# CARA_ctrl_v1_2.net
KiCad netlist of a schematic drawn in EAGLE
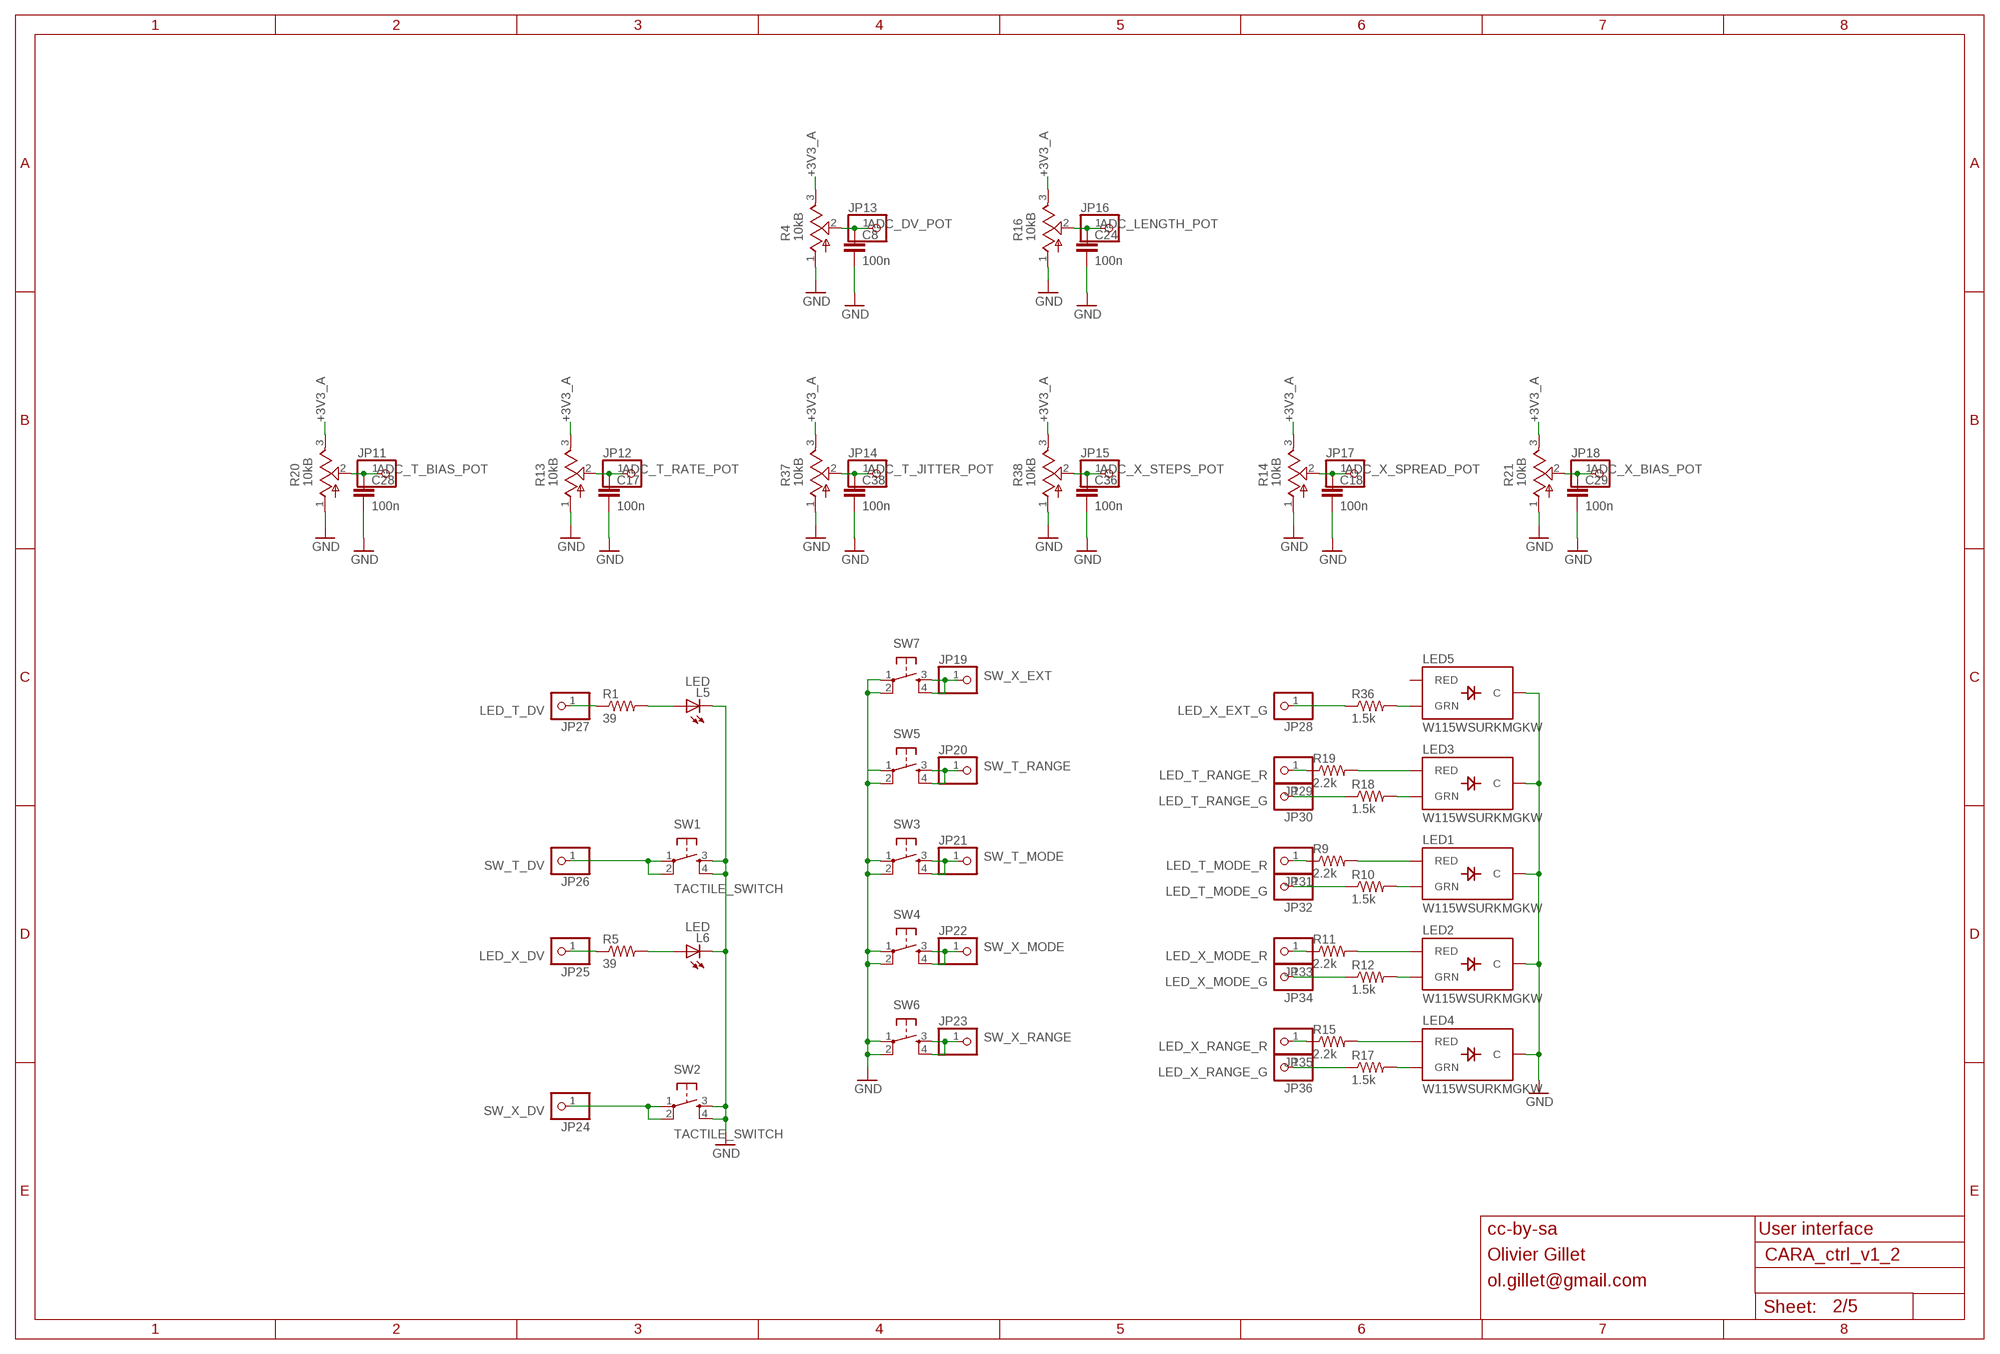
[diagram p0: schematic, sheet 2]
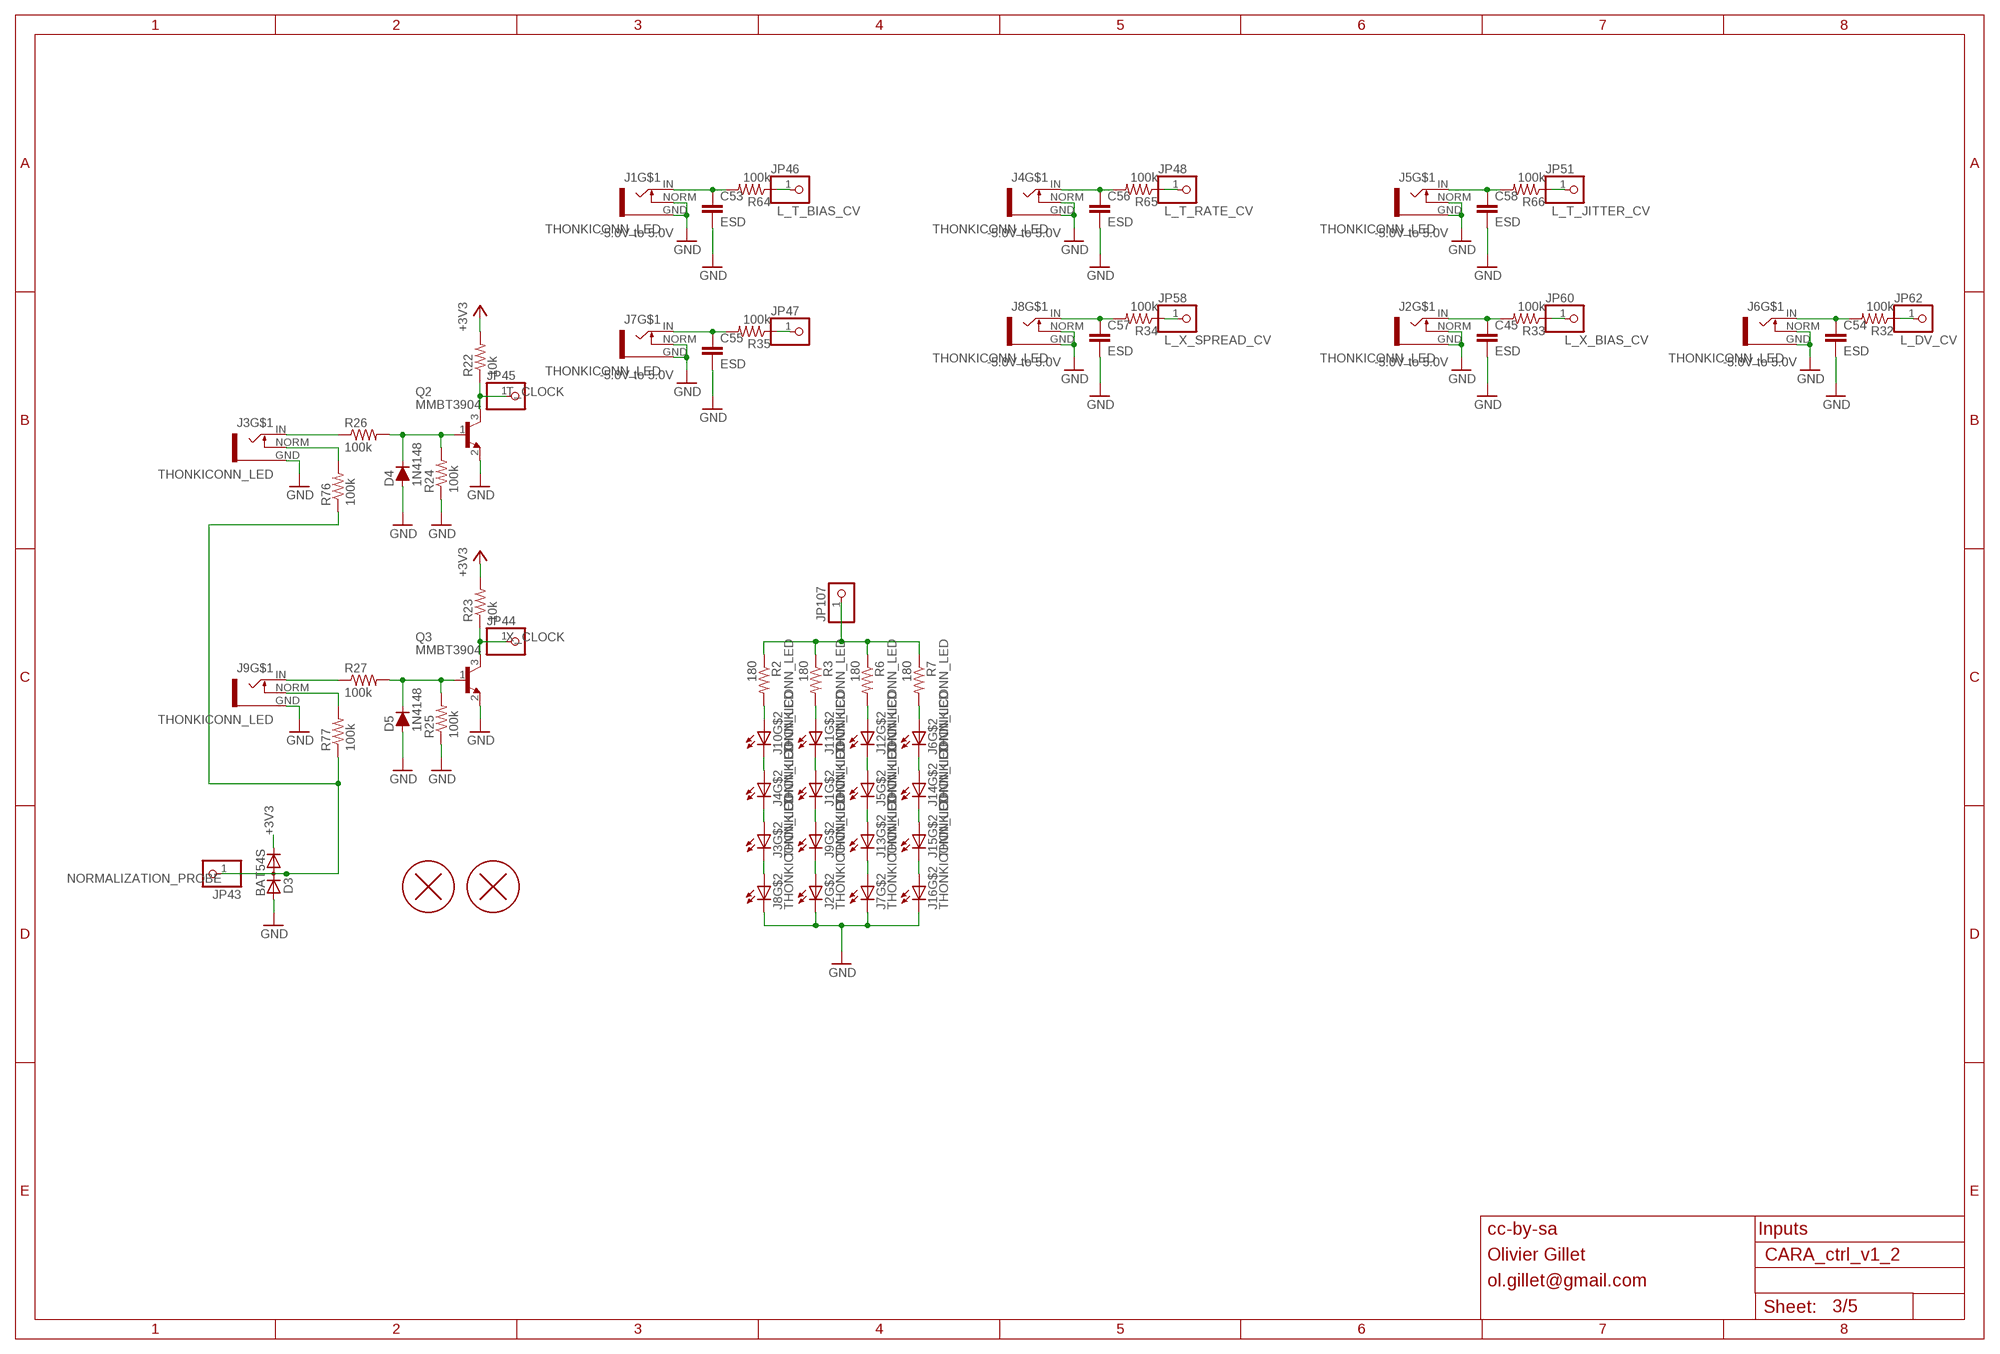
[diagram p1: schematic, sheet 3]
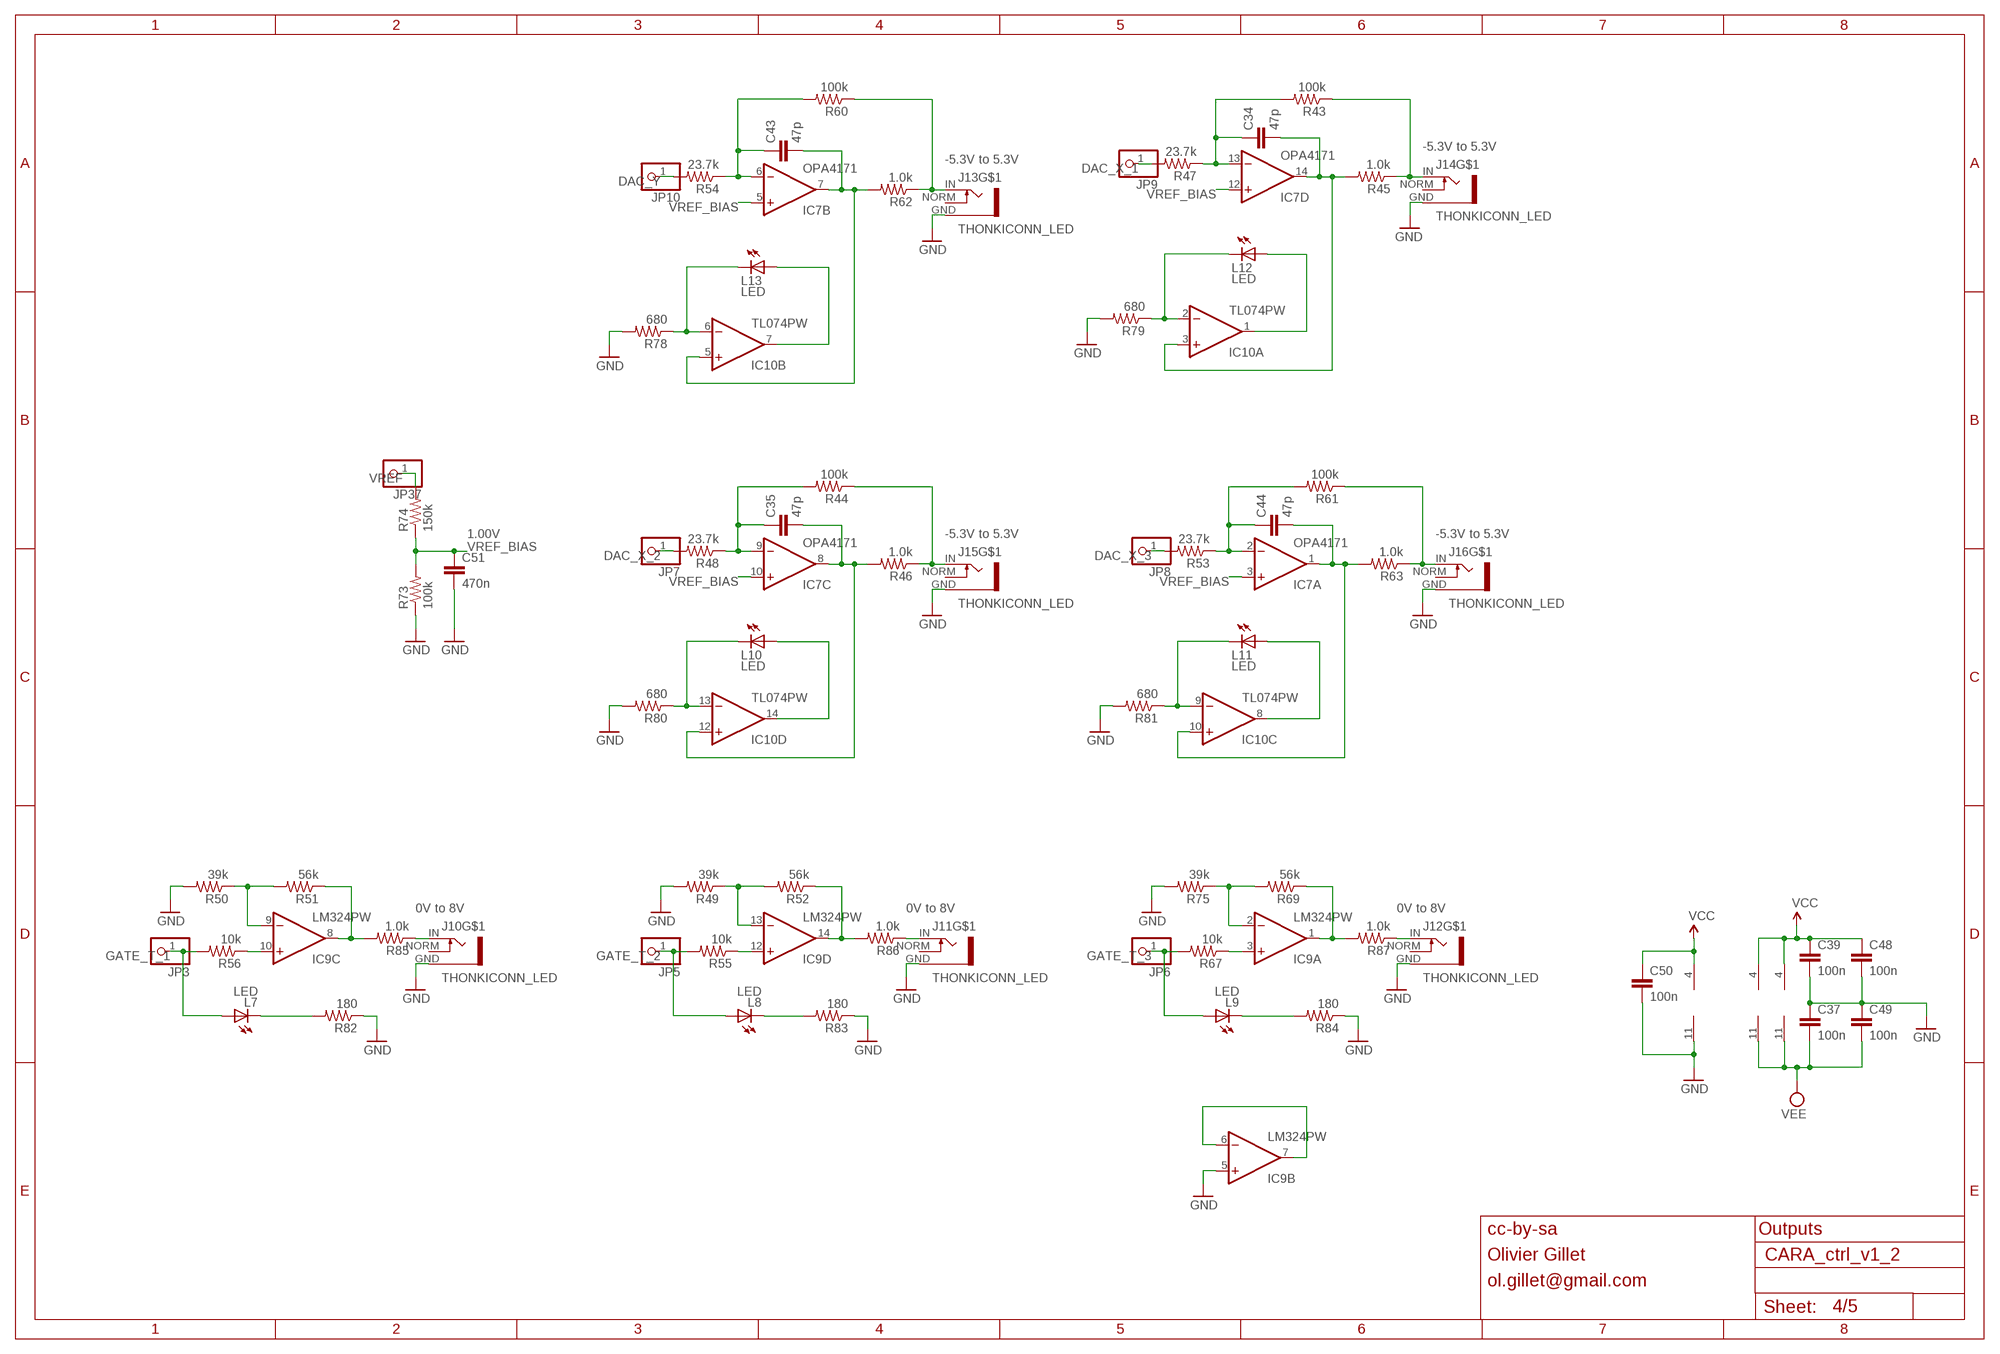
[diagram p2: schematic, sheet 4]
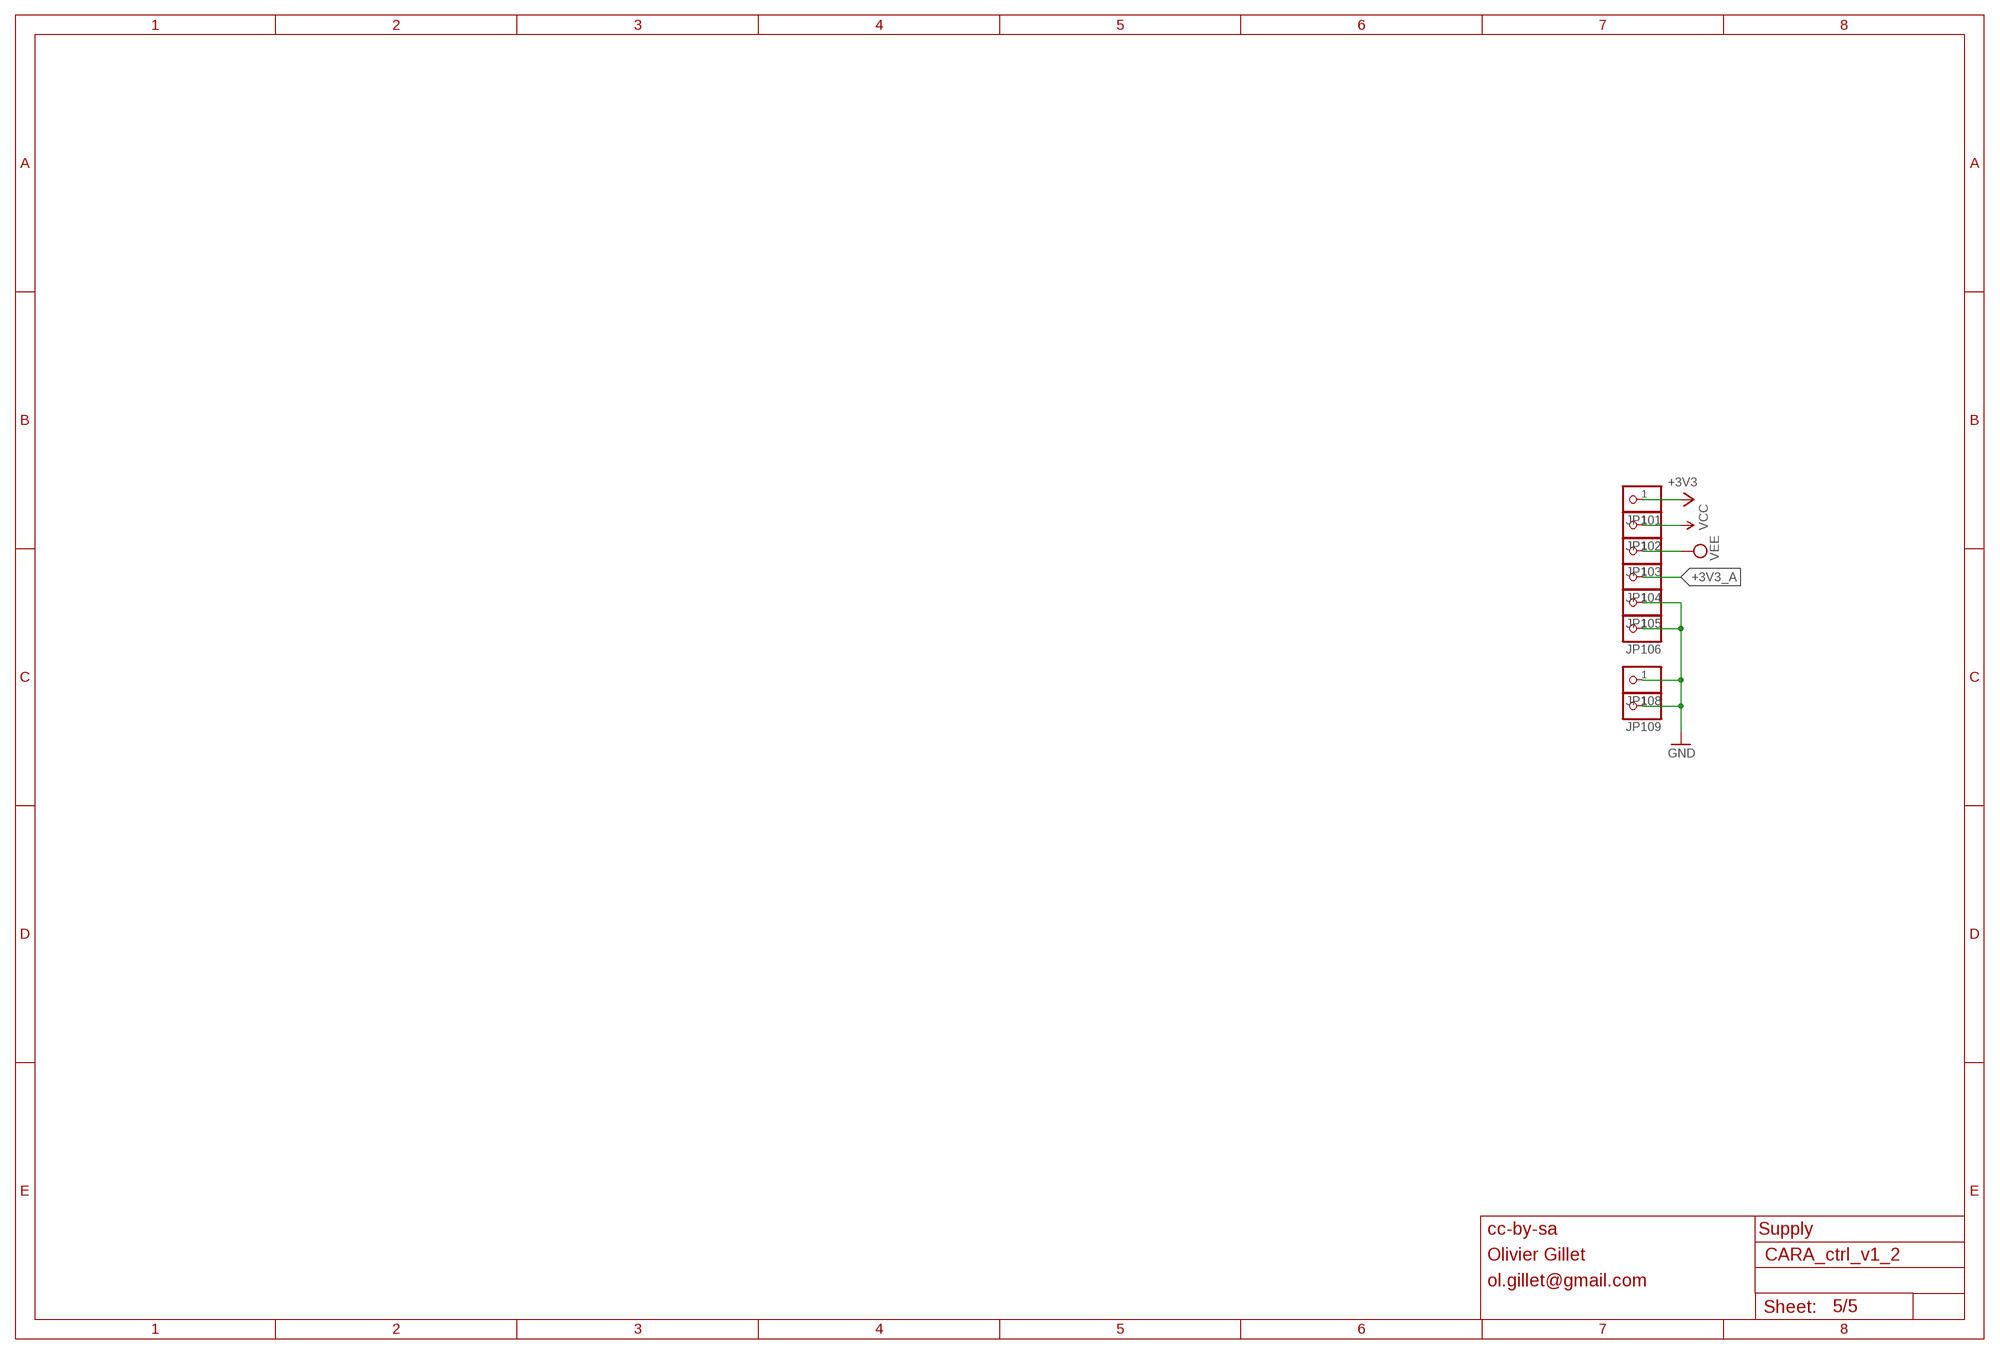
[diagram p3: schematic, sheet 5]

(export (version "E")
  (design (tool "Eeschema 10.0.6"))
  (components
    (comp (ref "C8")
      (value "100n")
      (footprint "eagle-import:RESISTOR_0603")
      (libsource (lib "eagle-import") (part "CAPACITOR"))
    )
    (comp (ref "C17")
      (value "100n")
      (footprint "eagle-import:RESISTOR_0603")
      (libsource (lib "eagle-import") (part "CAPACITOR"))
    )
    (comp (ref "C18")
      (value "100n")
      (footprint "eagle-import:RESISTOR_0603")
      (libsource (lib "eagle-import") (part "CAPACITOR"))
    )
    (comp (ref "C24")
      (value "100n")
      (footprint "eagle-import:RESISTOR_0603")
      (libsource (lib "eagle-import") (part "CAPACITOR"))
    )
    (comp (ref "C28")
      (value "100n")
      (footprint "eagle-import:RESISTOR_0603")
      (libsource (lib "eagle-import") (part "CAPACITOR"))
    )
    (comp (ref "C29")
      (value "100n")
      (footprint "eagle-import:RESISTOR_0603")
      (libsource (lib "eagle-import") (part "CAPACITOR"))
    )
    (comp (ref "C36")
      (value "100n")
      (footprint "eagle-import:RESISTOR_0603")
      (libsource (lib "eagle-import") (part "CAPACITOR"))
    )
    (comp (ref "C38")
      (value "100n")
      (footprint "eagle-import:RESISTOR_0603")
      (libsource (lib "eagle-import") (part "CAPACITOR"))
    )
    (comp (ref "JP11")
      (value "PINHD-1X1")
      (footprint "eagle-import:1X01")
      (libsource (lib "eagle-import") (part "PINHD-1X1"))
    )
    (comp (ref "JP12")
      (value "PINHD-1X1")
      (footprint "eagle-import:1X01")
      (libsource (lib "eagle-import") (part "PINHD-1X1"))
    )
    (comp (ref "JP13")
      (value "PINHD-1X1")
      (footprint "eagle-import:1X01")
      (libsource (lib "eagle-import") (part "PINHD-1X1"))
    )
    (comp (ref "JP14")
      (value "PINHD-1X1")
      (footprint "eagle-import:1X01")
      (libsource (lib "eagle-import") (part "PINHD-1X1"))
    )
    (comp (ref "JP15")
      (value "PINHD-1X1")
      (footprint "eagle-import:1X01")
      (libsource (lib "eagle-import") (part "PINHD-1X1"))
    )
    (comp (ref "JP16")
      (value "PINHD-1X1")
      (footprint "eagle-import:1X01")
      (libsource (lib "eagle-import") (part "PINHD-1X1"))
    )
    (comp (ref "JP17")
      (value "PINHD-1X1")
      (footprint "eagle-import:1X01")
      (libsource (lib "eagle-import") (part "PINHD-1X1"))
    )
    (comp (ref "JP18")
      (value "PINHD-1X1")
      (footprint "eagle-import:1X01")
      (libsource (lib "eagle-import") (part "PINHD-1X1"))
    )
    (comp (ref "JP19")
      (value "PINHD-1X1")
      (footprint "eagle-import:1X01")
      (libsource (lib "eagle-import") (part "PINHD-1X1"))
    )
    (comp (ref "JP20")
      (value "PINHD-1X1")
      (footprint "eagle-import:1X01")
      (libsource (lib "eagle-import") (part "PINHD-1X1"))
    )
    (comp (ref "JP21")
      (value "PINHD-1X1")
      (footprint "eagle-import:1X01")
      (libsource (lib "eagle-import") (part "PINHD-1X1"))
    )
    (comp (ref "JP22")
      (value "PINHD-1X1")
      (footprint "eagle-import:1X01")
      (libsource (lib "eagle-import") (part "PINHD-1X1"))
    )
    (comp (ref "JP23")
      (value "PINHD-1X1")
      (footprint "eagle-import:1X01")
      (libsource (lib "eagle-import") (part "PINHD-1X1"))
    )
    (comp (ref "JP24")
      (value "PINHD-1X1")
      (footprint "eagle-import:1X01")
      (libsource (lib "eagle-import") (part "PINHD-1X1"))
    )
    (comp (ref "JP25")
      (value "PINHD-1X1")
      (footprint "eagle-import:1X01")
      (libsource (lib "eagle-import") (part "PINHD-1X1"))
    )
    (comp (ref "JP26")
      (value "PINHD-1X1")
      (footprint "eagle-import:1X01")
      (libsource (lib "eagle-import") (part "PINHD-1X1"))
    )
    (comp (ref "JP27")
      (value "PINHD-1X1")
      (footprint "eagle-import:1X01")
      (libsource (lib "eagle-import") (part "PINHD-1X1"))
    )
    (comp (ref "JP28")
      (value "PINHD-1X1")
      (footprint "eagle-import:1X01")
      (libsource (lib "eagle-import") (part "PINHD-1X1"))
    )
    (comp (ref "JP29")
      (value "PINHD-1X1")
      (footprint "eagle-import:1X01")
      (libsource (lib "eagle-import") (part "PINHD-1X1"))
    )
    (comp (ref "JP30")
      (value "PINHD-1X1")
      (footprint "eagle-import:1X01")
      (libsource (lib "eagle-import") (part "PINHD-1X1"))
    )
    (comp (ref "JP31")
      (value "PINHD-1X1")
      (footprint "eagle-import:1X01")
      (libsource (lib "eagle-import") (part "PINHD-1X1"))
    )
    (comp (ref "JP32")
      (value "PINHD-1X1")
      (footprint "eagle-import:1X01")
      (libsource (lib "eagle-import") (part "PINHD-1X1"))
    )
    (comp (ref "JP33")
      (value "PINHD-1X1")
      (footprint "eagle-import:1X01")
      (libsource (lib "eagle-import") (part "PINHD-1X1"))
    )
    (comp (ref "JP34")
      (value "PINHD-1X1")
      (footprint "eagle-import:1X01")
      (libsource (lib "eagle-import") (part "PINHD-1X1"))
    )
    (comp (ref "JP35")
      (value "PINHD-1X1")
      (footprint "eagle-import:1X01")
      (libsource (lib "eagle-import") (part "PINHD-1X1"))
    )
    (comp (ref "JP36")
      (value "PINHD-1X1")
      (footprint "eagle-import:1X01")
      (libsource (lib "eagle-import") (part "PINHD-1X1"))
    )
    (comp (ref "L5")
      (value "LED")
      (footprint "eagle-import:LED_3MM")
      (libsource (lib "eagle-import") (part "LED"))
    )
    (comp (ref "L6")
      (value "LED")
      (footprint "eagle-import:LED_3MM")
      (libsource (lib "eagle-import") (part "LED"))
    )
    (comp (ref "LED1")
      (value "W115WSURKMGKW")
      (footprint "eagle-import:LED_BICOLOR")
      (libsource (lib "eagle-import") (part "LED_BICOLOR_THROUGHHOLE"))
    )
    (comp (ref "LED2")
      (value "W115WSURKMGKW")
      (footprint "eagle-import:LED_BICOLOR")
      (libsource (lib "eagle-import") (part "LED_BICOLOR_THROUGHHOLE"))
    )
    (comp (ref "LED3")
      (value "W115WSURKMGKW")
      (footprint "eagle-import:LED_BICOLOR")
      (libsource (lib "eagle-import") (part "LED_BICOLOR_THROUGHHOLE"))
    )
    (comp (ref "LED4")
      (value "W115WSURKMGKW")
      (footprint "eagle-import:LED_BICOLOR")
      (libsource (lib "eagle-import") (part "LED_BICOLOR_THROUGHHOLE"))
    )
    (comp (ref "LED5")
      (value "W115WSURKMGKW")
      (footprint "eagle-import:LED_BICOLOR")
      (libsource (lib "eagle-import") (part "LED_BICOLOR_THROUGHHOLE"))
    )
    (comp (ref "R1")
      (value "39")
      (footprint "eagle-import:RESISTOR_0603")
      (libsource (lib "eagle-import") (part "RESISTOR"))
    )
    (comp (ref "R4")
      (value "10kB")
      (footprint "eagle-import:ALPS_POT_VERTICAL")
      (libsource (lib "eagle-import") (part "POT_VERTICAL"))
    )
    (comp (ref "R5")
      (value "39")
      (footprint "eagle-import:RESISTOR_0603")
      (libsource (lib "eagle-import") (part "RESISTOR"))
    )
    (comp (ref "R9")
      (value "2.2k")
      (footprint "eagle-import:RESISTOR_0603")
      (libsource (lib "eagle-import") (part "RESISTOR"))
    )
    (comp (ref "R10")
      (value "1.5k")
      (footprint "eagle-import:RESISTOR_0603")
      (libsource (lib "eagle-import") (part "RESISTOR"))
    )
    (comp (ref "R11")
      (value "2.2k")
      (footprint "eagle-import:RESISTOR_0603")
      (libsource (lib "eagle-import") (part "RESISTOR"))
    )
    (comp (ref "R12")
      (value "1.5k")
      (footprint "eagle-import:RESISTOR_0603")
      (libsource (lib "eagle-import") (part "RESISTOR"))
    )
    (comp (ref "R13")
      (value "10kB")
      (footprint "eagle-import:ALPS_POT_VERTICAL")
      (libsource (lib "eagle-import") (part "POT_VERTICAL"))
    )
    (comp (ref "R14")
      (value "10kB")
      (footprint "eagle-import:ALPS_POT_VERTICAL")
      (libsource (lib "eagle-import") (part "POT_VERTICAL"))
    )
    (comp (ref "R15")
      (value "2.2k")
      (footprint "eagle-import:RESISTOR_0603")
      (libsource (lib "eagle-import") (part "RESISTOR"))
    )
    (comp (ref "R16")
      (value "10kB")
      (footprint "eagle-import:ALPS_POT_VERTICAL")
      (libsource (lib "eagle-import") (part "POT_VERTICAL"))
    )
    (comp (ref "R17")
      (value "1.5k")
      (footprint "eagle-import:RESISTOR_0603")
      (libsource (lib "eagle-import") (part "RESISTOR"))
    )
    (comp (ref "R18")
      (value "1.5k")
      (footprint "eagle-import:RESISTOR_0603")
      (libsource (lib "eagle-import") (part "RESISTOR"))
    )
    (comp (ref "R19")
      (value "2.2k")
      (footprint "eagle-import:RESISTOR_0603")
      (libsource (lib "eagle-import") (part "RESISTOR"))
    )
    (comp (ref "R20")
      (value "10kB")
      (footprint "eagle-import:ALPS_POT_VERTICAL")
      (libsource (lib "eagle-import") (part "POT_VERTICAL"))
    )
    (comp (ref "R21")
      (value "10kB")
      (footprint "eagle-import:ALPS_POT_VERTICAL")
      (libsource (lib "eagle-import") (part "POT_VERTICAL"))
    )
    (comp (ref "R36")
      (value "1.5k")
      (footprint "eagle-import:RESISTOR_0603")
      (libsource (lib "eagle-import") (part "RESISTOR"))
    )
    (comp (ref "R37")
      (value "10kB")
      (footprint "eagle-import:ALPS_POT_VERTICAL")
      (libsource (lib "eagle-import") (part "POT_VERTICAL"))
    )
    (comp (ref "R38")
      (value "10kB")
      (footprint "eagle-import:ALPS_POT_VERTICAL")
      (libsource (lib "eagle-import") (part "POT_VERTICAL"))
    )
    (comp (ref "SW1")
      (value "TACTILE_SWITCH")
      (footprint "eagle-import:TACTILE-PTH")
      (libsource (lib "eagle-import") (part "TACTILE_SWITCH"))
    )
    (comp (ref "SW2")
      (value "TACTILE_SWITCH")
      (footprint "eagle-import:TACTILE-PTH")
      (libsource (lib "eagle-import") (part "TACTILE_SWITCH"))
    )
    (comp (ref "SW3")
      (value "TACTILE_SWITCH")
      (footprint "eagle-import:TACTILE-PTH")
      (libsource (lib "eagle-import") (part "TACTILE_SWITCH"))
    )
    (comp (ref "SW4")
      (value "TACTILE_SWITCH")
      (footprint "eagle-import:TACTILE-PTH")
      (libsource (lib "eagle-import") (part "TACTILE_SWITCH"))
    )
    (comp (ref "SW5")
      (value "TACTILE_SWITCH")
      (footprint "eagle-import:TACTILE-PTH")
      (libsource (lib "eagle-import") (part "TACTILE_SWITCH"))
    )
    (comp (ref "SW6")
      (value "TACTILE_SWITCH")
      (footprint "eagle-import:TACTILE-PTH")
      (libsource (lib "eagle-import") (part "TACTILE_SWITCH"))
    )
    (comp (ref "SW7")
      (value "TACTILE_SWITCH")
      (footprint "eagle-import:TACTILE-PTH")
      (libsource (lib "eagle-import") (part "TACTILE_SWITCH"))
    )
    (comp (ref "JP101")
      (value "PINHD-1X1")
      (footprint "eagle-import:1X01")
      (libsource (lib "eagle-import") (part "PINHD-1X1"))
    )
    (comp (ref "JP102")
      (value "PINHD-1X1")
      (footprint "eagle-import:1X01")
      (libsource (lib "eagle-import") (part "PINHD-1X1"))
    )
    (comp (ref "JP103")
      (value "PINHD-1X1")
      (footprint "eagle-import:1X01")
      (libsource (lib "eagle-import") (part "PINHD-1X1"))
    )
    (comp (ref "JP104")
      (value "PINHD-1X1")
      (footprint "eagle-import:1X01")
      (libsource (lib "eagle-import") (part "PINHD-1X1"))
    )
    (comp (ref "JP105")
      (value "PINHD-1X1")
      (footprint "eagle-import:1X01")
      (libsource (lib "eagle-import") (part "PINHD-1X1"))
    )
    (comp (ref "JP106")
      (value "PINHD-1X1")
      (footprint "eagle-import:1X01")
      (libsource (lib "eagle-import") (part "PINHD-1X1"))
    )
    (comp (ref "JP108")
      (value "PINHD-1X1")
      (footprint "eagle-import:1X01")
      (libsource (lib "eagle-import") (part "PINHD-1X1"))
    )
    (comp (ref "JP109")
      (value "PINHD-1X1")
      (footprint "eagle-import:1X01")
      (libsource (lib "eagle-import") (part "PINHD-1X1"))
    )
    (comp (ref "C45")
      (value "ESD")
      (footprint "eagle-import:RESISTOR_0603")
      (libsource (lib "eagle-import") (part "CAPACITOR"))
    )
    (comp (ref "C53")
      (value "ESD")
      (footprint "eagle-import:RESISTOR_0603")
      (libsource (lib "eagle-import") (part "CAPACITOR"))
    )
    (comp (ref "C54")
      (value "ESD")
      (footprint "eagle-import:RESISTOR_0603")
      (libsource (lib "eagle-import") (part "CAPACITOR"))
    )
    (comp (ref "C55")
      (value "ESD")
      (footprint "eagle-import:RESISTOR_0603")
      (libsource (lib "eagle-import") (part "CAPACITOR"))
    )
    (comp (ref "C56")
      (value "ESD")
      (footprint "eagle-import:RESISTOR_0603")
      (libsource (lib "eagle-import") (part "CAPACITOR"))
    )
    (comp (ref "C57")
      (value "ESD")
      (footprint "eagle-import:RESISTOR_0603")
      (libsource (lib "eagle-import") (part "CAPACITOR"))
    )
    (comp (ref "C58")
      (value "ESD")
      (footprint "eagle-import:RESISTOR_0603")
      (libsource (lib "eagle-import") (part "CAPACITOR"))
    )
    (comp (ref "D3")
      (value "BAT54S")
      (footprint "eagle-import:SOT23")
      (libsource (lib "eagle-import") (part "DIODE_2CACA-SOT23"))
    )
    (comp (ref "D4")
      (value "1N4148")
      (footprint "eagle-import:SOD123")
      (libsource (lib "eagle-import") (part "DIODE"))
    )
    (comp (ref "D5")
      (value "1N4148")
      (footprint "eagle-import:SOD123")
      (libsource (lib "eagle-import") (part "DIODE"))
    )
    (comp (ref "H1")
      (value "PCB_SCREW")
      (footprint "eagle-import:PCB_SCREW")
      (libsource (lib "eagle-import") (part "PCB_SCREW"))
    )
    (comp (ref "H2")
      (value "PCB_SCREW")
      (footprint "eagle-import:PCB_SCREW")
      (libsource (lib "eagle-import") (part "PCB_SCREW"))
    )
    (comp (ref "J1")
      (value "THONKICONN_LED")
      (footprint "eagle-import:LED_JACK")
      (libsource (lib "eagle-import") (part "THONKICONN_LED"))
    )
    (comp (ref "J2")
      (value "THONKICONN_LED")
      (footprint "eagle-import:LED_JACK")
      (libsource (lib "eagle-import") (part "THONKICONN_LED"))
    )
    (comp (ref "J3")
      (value "THONKICONN_LED")
      (footprint "eagle-import:LED_JACK")
      (libsource (lib "eagle-import") (part "THONKICONN_LED"))
    )
    (comp (ref "J4")
      (value "THONKICONN_LED")
      (footprint "eagle-import:LED_JACK")
      (libsource (lib "eagle-import") (part "THONKICONN_LED"))
    )
    (comp (ref "J5")
      (value "THONKICONN_LED")
      (footprint "eagle-import:LED_JACK")
      (libsource (lib "eagle-import") (part "THONKICONN_LED"))
    )
    (comp (ref "J6")
      (value "THONKICONN_LED")
      (footprint "eagle-import:LED_JACK")
      (libsource (lib "eagle-import") (part "THONKICONN_LED"))
    )
    (comp (ref "J7")
      (value "THONKICONN_LED")
      (footprint "eagle-import:LED_JACK")
      (libsource (lib "eagle-import") (part "THONKICONN_LED"))
    )
    (comp (ref "J8")
      (value "THONKICONN_LED")
      (footprint "eagle-import:LED_JACK")
      (libsource (lib "eagle-import") (part "THONKICONN_LED"))
    )
    (comp (ref "J9")
      (value "THONKICONN_LED")
      (footprint "eagle-import:LED_JACK")
      (libsource (lib "eagle-import") (part "THONKICONN_LED"))
    )
    (comp (ref "J10")
      (value "THONKICONN_LED")
      (footprint "eagle-import:LED_JACK")
      (libsource (lib "eagle-import") (part "THONKICONN_LED"))
    )
    (comp (ref "J11")
      (value "THONKICONN_LED")
      (footprint "eagle-import:LED_JACK")
      (libsource (lib "eagle-import") (part "THONKICONN_LED"))
    )
    (comp (ref "J12")
      (value "THONKICONN_LED")
      (footprint "eagle-import:LED_JACK")
      (libsource (lib "eagle-import") (part "THONKICONN_LED"))
    )
    (comp (ref "J13")
      (value "THONKICONN_LED")
      (footprint "eagle-import:LED_JACK")
      (libsource (lib "eagle-import") (part "THONKICONN_LED"))
    )
    (comp (ref "J14")
      (value "THONKICONN_LED")
      (footprint "eagle-import:LED_JACK")
      (libsource (lib "eagle-import") (part "THONKICONN_LED"))
    )
    (comp (ref "J15")
      (value "THONKICONN_LED")
      (footprint "eagle-import:LED_JACK")
      (libsource (lib "eagle-import") (part "THONKICONN_LED"))
    )
    (comp (ref "J16")
      (value "THONKICONN_LED")
      (footprint "eagle-import:LED_JACK")
      (libsource (lib "eagle-import") (part "THONKICONN_LED"))
    )
    (comp (ref "JP43")
      (value "PINHD-1X1")
      (footprint "eagle-import:1X01")
      (libsource (lib "eagle-import") (part "PINHD-1X1"))
    )
    (comp (ref "JP44")
      (value "PINHD-1X1")
      (footprint "eagle-import:1X01")
      (libsource (lib "eagle-import") (part "PINHD-1X1"))
    )
    (comp (ref "JP45")
      (value "PINHD-1X1")
      (footprint "eagle-import:1X01")
      (libsource (lib "eagle-import") (part "PINHD-1X1"))
    )
    (comp (ref "JP46")
      (value "PINHD-1X1")
      (footprint "eagle-import:1X01")
      (libsource (lib "eagle-import") (part "PINHD-1X1"))
    )
    (comp (ref "JP47")
      (value "PINHD-1X1")
      (footprint "eagle-import:1X01")
      (libsource (lib "eagle-import") (part "PINHD-1X1"))
    )
    (comp (ref "JP48")
      (value "PINHD-1X1")
      (footprint "eagle-import:1X01")
      (libsource (lib "eagle-import") (part "PINHD-1X1"))
    )
    (comp (ref "JP51")
      (value "PINHD-1X1")
      (footprint "eagle-import:1X01")
      (libsource (lib "eagle-import") (part "PINHD-1X1"))
    )
    (comp (ref "JP58")
      (value "PINHD-1X1")
      (footprint "eagle-import:1X01")
      (libsource (lib "eagle-import") (part "PINHD-1X1"))
    )
    (comp (ref "JP60")
      (value "PINHD-1X1")
      (footprint "eagle-import:1X01")
      (libsource (lib "eagle-import") (part "PINHD-1X1"))
    )
    (comp (ref "JP62")
      (value "PINHD-1X1")
      (footprint "eagle-import:1X01")
      (libsource (lib "eagle-import") (part "PINHD-1X1"))
    )
    (comp (ref "JP107")
      (value "PINHD-1X1")
      (footprint "eagle-import:1X01")
      (libsource (lib "eagle-import") (part "PINHD-1X1"))
    )
    (comp (ref "Q2")
      (value "MMBT3904")
      (footprint "eagle-import:SOT23")
      (libsource (lib "eagle-import") (part "MMBT3904SOT23"))
    )
    (comp (ref "Q3")
      (value "MMBT3904")
      (footprint "eagle-import:SOT23")
      (libsource (lib "eagle-import") (part "MMBT3904SOT23"))
    )
    (comp (ref "R2")
      (value "180")
      (footprint "eagle-import:RESISTOR_0603")
      (libsource (lib "eagle-import") (part "RESISTOR"))
    )
    (comp (ref "R3")
      (value "180")
      (footprint "eagle-import:RESISTOR_0603")
      (libsource (lib "eagle-import") (part "RESISTOR"))
    )
    (comp (ref "R6")
      (value "180")
      (footprint "eagle-import:RESISTOR_0603")
      (libsource (lib "eagle-import") (part "RESISTOR"))
    )
    (comp (ref "R7")
      (value "180")
      (footprint "eagle-import:RESISTOR_0603")
      (libsource (lib "eagle-import") (part "RESISTOR"))
    )
    (comp (ref "R22")
      (value "10k")
      (footprint "eagle-import:RESISTOR_0603")
      (libsource (lib "eagle-import") (part "RESISTOR"))
    )
    (comp (ref "R23")
      (value "10k")
      (footprint "eagle-import:RESISTOR_0603")
      (libsource (lib "eagle-import") (part "RESISTOR"))
    )
    (comp (ref "R24")
      (value "100k")
      (footprint "eagle-import:RESISTOR_0603")
      (libsource (lib "eagle-import") (part "RESISTOR"))
    )
    (comp (ref "R25")
      (value "100k")
      (footprint "eagle-import:RESISTOR_0603")
      (libsource (lib "eagle-import") (part "RESISTOR"))
    )
    (comp (ref "R26")
      (value "100k")
      (footprint "eagle-import:RESISTOR_0603")
      (libsource (lib "eagle-import") (part "RESISTOR"))
    )
    (comp (ref "R27")
      (value "100k")
      (footprint "eagle-import:RESISTOR_0603")
      (libsource (lib "eagle-import") (part "RESISTOR"))
    )
    (comp (ref "R32")
      (value "100k")
      (footprint "eagle-import:RESISTOR_0603")
      (libsource (lib "eagle-import") (part "RESISTOR"))
    )
    (comp (ref "R33")
      (value "100k")
      (footprint "eagle-import:RESISTOR_0603")
      (libsource (lib "eagle-import") (part "RESISTOR"))
    )
    (comp (ref "R34")
      (value "100k")
      (footprint "eagle-import:RESISTOR_0603")
      (libsource (lib "eagle-import") (part "RESISTOR"))
    )
    (comp (ref "R35")
      (value "100k")
      (footprint "eagle-import:RESISTOR_0603")
      (libsource (lib "eagle-import") (part "RESISTOR"))
    )
    (comp (ref "R64")
      (value "100k")
      (footprint "eagle-import:RESISTOR_0603")
      (libsource (lib "eagle-import") (part "RESISTOR"))
    )
    (comp (ref "R65")
      (value "100k")
      (footprint "eagle-import:RESISTOR_0603")
      (libsource (lib "eagle-import") (part "RESISTOR"))
    )
    (comp (ref "R66")
      (value "100k")
      (footprint "eagle-import:RESISTOR_0603")
      (libsource (lib "eagle-import") (part "RESISTOR"))
    )
    (comp (ref "R76")
      (value "100k")
      (footprint "eagle-import:RESISTOR_0603")
      (libsource (lib "eagle-import") (part "RESISTOR"))
    )
    (comp (ref "R77")
      (value "100k")
      (footprint "eagle-import:RESISTOR_0603")
      (libsource (lib "eagle-import") (part "RESISTOR"))
    )
    (comp (ref "C34")
      (value "47p")
      (footprint "eagle-import:RESISTOR_0603")
      (libsource (lib "eagle-import") (part "CAPACITOR"))
    )
    (comp (ref "C35")
      (value "47p")
      (footprint "eagle-import:RESISTOR_0603")
      (libsource (lib "eagle-import") (part "CAPACITOR"))
    )
    (comp (ref "C37")
      (value "100n")
      (footprint "eagle-import:RESISTOR_0603")
      (libsource (lib "eagle-import") (part "CAPACITOR"))
    )
    (comp (ref "C39")
      (value "100n")
      (footprint "eagle-import:RESISTOR_0603")
      (libsource (lib "eagle-import") (part "CAPACITOR"))
    )
    (comp (ref "C43")
      (value "47p")
      (footprint "eagle-import:RESISTOR_0603")
      (libsource (lib "eagle-import") (part "CAPACITOR"))
    )
    (comp (ref "C44")
      (value "47p")
      (footprint "eagle-import:RESISTOR_0603")
      (libsource (lib "eagle-import") (part "CAPACITOR"))
    )
    (comp (ref "C48")
      (value "100n")
      (footprint "eagle-import:RESISTOR_0603")
      (libsource (lib "eagle-import") (part "CAPACITOR"))
    )
    (comp (ref "C49")
      (value "100n")
      (footprint "eagle-import:RESISTOR_0603")
      (libsource (lib "eagle-import") (part "CAPACITOR"))
    )
    (comp (ref "C50")
      (value "100n")
      (footprint "eagle-import:RESISTOR_0603")
      (libsource (lib "eagle-import") (part "CAPACITOR"))
    )
    (comp (ref "C51")
      (value "470n")
      (footprint "eagle-import:RESISTOR_0603")
      (libsource (lib "eagle-import") (part "CAPACITOR"))
    )
    (comp (ref "IC7")
      (value "OPA4171")
      (footprint "eagle-import:TSSOP14_065")
      (libsource (lib "eagle-import") (part "TL074PW"))
    )
    (comp (ref "IC9")
      (value "LM324PW")
      (footprint "eagle-import:TSSOP14_065")
      (libsource (lib "eagle-import") (part "TL074PW"))
    )
    (comp (ref "IC10")
      (value "TL074PW")
      (footprint "eagle-import:TSSOP14_065")
      (libsource (lib "eagle-import") (part "TL074PW"))
    )
    (comp (ref "JP3")
      (value "PINHD-1X1")
      (footprint "eagle-import:1X01")
      (libsource (lib "eagle-import") (part "PINHD-1X1"))
    )
    (comp (ref "JP5")
      (value "PINHD-1X1")
      (footprint "eagle-import:1X01")
      (libsource (lib "eagle-import") (part "PINHD-1X1"))
    )
    (comp (ref "JP6")
      (value "PINHD-1X1")
      (footprint "eagle-import:1X01")
      (libsource (lib "eagle-import") (part "PINHD-1X1"))
    )
    (comp (ref "JP7")
      (value "PINHD-1X1")
      (footprint "eagle-import:1X01")
      (libsource (lib "eagle-import") (part "PINHD-1X1"))
    )
    (comp (ref "JP8")
      (value "PINHD-1X1")
      (footprint "eagle-import:1X01")
      (libsource (lib "eagle-import") (part "PINHD-1X1"))
    )
    (comp (ref "JP9")
      (value "PINHD-1X1")
      (footprint "eagle-import:1X01")
      (libsource (lib "eagle-import") (part "PINHD-1X1"))
    )
    (comp (ref "JP10")
      (value "PINHD-1X1")
      (footprint "eagle-import:1X01")
      (libsource (lib "eagle-import") (part "PINHD-1X1"))
    )
    (comp (ref "JP37")
      (value "PINHD-1X1")
      (footprint "eagle-import:1X01")
      (libsource (lib "eagle-import") (part "PINHD-1X1"))
    )
    (comp (ref "L7")
      (value "LED")
      (footprint "eagle-import:LED_3MM")
      (libsource (lib "eagle-import") (part "LED"))
    )
    (comp (ref "L8")
      (value "LED")
      (footprint "eagle-import:LED_3MM")
      (libsource (lib "eagle-import") (part "LED"))
    )
    (comp (ref "L9")
      (value "LED")
      (footprint "eagle-import:LED_3MM")
      (libsource (lib "eagle-import") (part "LED"))
    )
    (comp (ref "L10")
      (value "LED")
      (footprint "eagle-import:LED_3MM")
      (libsource (lib "eagle-import") (part "LED"))
    )
    (comp (ref "L11")
      (value "LED")
      (footprint "eagle-import:LED_3MM")
      (libsource (lib "eagle-import") (part "LED"))
    )
    (comp (ref "L12")
      (value "LED")
      (footprint "eagle-import:LED_3MM")
      (libsource (lib "eagle-import") (part "LED"))
    )
    (comp (ref "L13")
      (value "LED")
      (footprint "eagle-import:LED_3MM")
      (libsource (lib "eagle-import") (part "LED"))
    )
    (comp (ref "R43")
      (value "100k")
      (footprint "eagle-import:RESISTOR_0603")
      (libsource (lib "eagle-import") (part "RESISTOR"))
    )
    (comp (ref "R44")
      (value "100k")
      (footprint "eagle-import:RESISTOR_0603")
      (libsource (lib "eagle-import") (part "RESISTOR"))
    )
    (comp (ref "R45")
      (value "1.0k")
      (footprint "eagle-import:RESISTOR_0603")
      (libsource (lib "eagle-import") (part "RESISTOR"))
    )
    (comp (ref "R46")
      (value "1.0k")
      (footprint "eagle-import:RESISTOR_0603")
      (libsource (lib "eagle-import") (part "RESISTOR"))
    )
    (comp (ref "R47")
      (value "23.7k")
      (footprint "eagle-import:RESISTOR_0603")
      (libsource (lib "eagle-import") (part "RESISTOR"))
    )
    (comp (ref "R48")
      (value "23.7k")
      (footprint "eagle-import:RESISTOR_0603")
      (libsource (lib "eagle-import") (part "RESISTOR"))
    )
    (comp (ref "R49")
      (value "39k")
      (footprint "eagle-import:RESISTOR_0603")
      (libsource (lib "eagle-import") (part "RESISTOR"))
    )
    (comp (ref "R50")
      (value "39k")
      (footprint "eagle-import:RESISTOR_0603")
      (libsource (lib "eagle-import") (part "RESISTOR"))
    )
    (comp (ref "R51")
      (value "56k")
      (footprint "eagle-import:RESISTOR_0603")
      (libsource (lib "eagle-import") (part "RESISTOR"))
    )
    (comp (ref "R52")
      (value "56k")
      (footprint "eagle-import:RESISTOR_0603")
      (libsource (lib "eagle-import") (part "RESISTOR"))
    )
    (comp (ref "R53")
      (value "23.7k")
      (footprint "eagle-import:RESISTOR_0603")
      (libsource (lib "eagle-import") (part "RESISTOR"))
    )
    (comp (ref "R54")
      (value "23.7k")
      (footprint "eagle-import:RESISTOR_0603")
      (libsource (lib "eagle-import") (part "RESISTOR"))
    )
    (comp (ref "R55")
      (value "10k")
      (footprint "eagle-import:RESISTOR_0603")
      (libsource (lib "eagle-import") (part "RESISTOR"))
    )
    (comp (ref "R56")
      (value "10k")
      (footprint "eagle-import:RESISTOR_0603")
      (libsource (lib "eagle-import") (part "RESISTOR"))
    )
    (comp (ref "R60")
      (value "100k")
      (footprint "eagle-import:RESISTOR_0603")
      (libsource (lib "eagle-import") (part "RESISTOR"))
    )
    (comp (ref "R61")
      (value "100k")
      (footprint "eagle-import:RESISTOR_0603")
      (libsource (lib "eagle-import") (part "RESISTOR"))
    )
    (comp (ref "R62")
      (value "1.0k")
      (footprint "eagle-import:RESISTOR_0603")
      (libsource (lib "eagle-import") (part "RESISTOR"))
    )
    (comp (ref "R63")
      (value "1.0k")
      (footprint "eagle-import:RESISTOR_0603")
      (libsource (lib "eagle-import") (part "RESISTOR"))
    )
    (comp (ref "R67")
      (value "10k")
      (footprint "eagle-import:RESISTOR_0603")
      (libsource (lib "eagle-import") (part "RESISTOR"))
    )
    (comp (ref "R69")
      (value "56k")
      (footprint "eagle-import:RESISTOR_0603")
      (libsource (lib "eagle-import") (part "RESISTOR"))
    )
    (comp (ref "R73")
      (value "100k")
      (footprint "eagle-import:RESISTOR_0603")
      (libsource (lib "eagle-import") (part "RESISTOR"))
    )
    (comp (ref "R74")
      (value "150k")
      (footprint "eagle-import:RESISTOR_0603")
      (libsource (lib "eagle-import") (part "RESISTOR"))
    )
    (comp (ref "R75")
      (value "39k")
      (footprint "eagle-import:RESISTOR_0603")
      (libsource (lib "eagle-import") (part "RESISTOR"))
    )
    (comp (ref "R78")
      (value "680")
      (footprint "eagle-import:RESISTOR_0603")
      (libsource (lib "eagle-import") (part "RESISTOR"))
    )
    (comp (ref "R79")
      (value "680")
      (footprint "eagle-import:RESISTOR_0603")
      (libsource (lib "eagle-import") (part "RESISTOR"))
    )
    (comp (ref "R80")
      (value "680")
      (footprint "eagle-import:RESISTOR_0603")
      (libsource (lib "eagle-import") (part "RESISTOR"))
    )
    (comp (ref "R81")
      (value "680")
      (footprint "eagle-import:RESISTOR_0603")
      (libsource (lib "eagle-import") (part "RESISTOR"))
    )
    (comp (ref "R82")
      (value "180")
      (footprint "eagle-import:RESISTOR_0603")
      (libsource (lib "eagle-import") (part "RESISTOR"))
    )
    (comp (ref "R83")
      (value "180")
      (footprint "eagle-import:RESISTOR_0603")
      (libsource (lib "eagle-import") (part "RESISTOR"))
    )
    (comp (ref "R84")
      (value "180")
      (footprint "eagle-import:RESISTOR_0603")
      (libsource (lib "eagle-import") (part "RESISTOR"))
    )
    (comp (ref "R85")
      (value "1.0k")
      (footprint "eagle-import:RESISTOR_0603")
      (libsource (lib "eagle-import") (part "RESISTOR"))
    )
    (comp (ref "R86")
      (value "1.0k")
      (footprint "eagle-import:RESISTOR_0603")
      (libsource (lib "eagle-import") (part "RESISTOR"))
    )
    (comp (ref "R87")
      (value "1.0k")
      (footprint "eagle-import:RESISTOR_0603")
      (libsource (lib "eagle-import") (part "RESISTOR"))
    )
  )
  (nets
    (net (code "1") (name "+3V3") (class "Default")
      (node (ref "D3") (pin "2") (pinfunction "C_2") (pintype "passive"))
      (node (ref "JP101") (pin "1") (pinfunction "1_1") (pintype "passive"))
      (node (ref "R22") (pin "2") (pinfunction "2_2") (pintype "passive"))
      (node (ref "R23") (pin "2") (pinfunction "2_2") (pintype "passive"))
    )
    (net (code "2") (name "+3V3_A") (class "Default")
      (node (ref "JP104") (pin "1") (pinfunction "1_1") (pintype "passive"))
      (node (ref "R13") (pin "3") (pinfunction "B_3") (pintype "passive"))
      (node (ref "R14") (pin "3") (pinfunction "B_3") (pintype "passive"))
      (node (ref "R16") (pin "3") (pinfunction "B_3") (pintype "passive"))
      (node (ref "R20") (pin "3") (pinfunction "B_3") (pintype "passive"))
      (node (ref "R21") (pin "3") (pinfunction "B_3") (pintype "passive"))
      (node (ref "R37") (pin "3") (pinfunction "B_3") (pintype "passive"))
      (node (ref "R38") (pin "3") (pinfunction "B_3") (pintype "passive"))
      (node (ref "R4") (pin "3") (pinfunction "B_3") (pintype "passive"))
    )
    (net (code "3") (name "ADC_DV_POT") (class "Default")
      (node (ref "C8") (pin "1") (pinfunction "1_1") (pintype "passive"))
      (node (ref "JP13") (pin "1") (pinfunction "1_1") (pintype "passive"))
      (node (ref "R4") (pin "2") (pinfunction "W_2") (pintype "passive"))
    )
    (net (code "4") (name "ADC_LENGTH_POT") (class "Default")
      (node (ref "C24") (pin "1") (pinfunction "1_1") (pintype "passive"))
      (node (ref "JP16") (pin "1") (pinfunction "1_1") (pintype "passive"))
      (node (ref "R16") (pin "2") (pinfunction "W_2") (pintype "passive"))
    )
    (net (code "5") (name "ADC_T_BIAS_POT") (class "Default")
      (node (ref "C28") (pin "1") (pinfunction "1_1") (pintype "passive"))
      (node (ref "JP11") (pin "1") (pinfunction "1_1") (pintype "passive"))
      (node (ref "R20") (pin "2") (pinfunction "W_2") (pintype "passive"))
    )
    (net (code "6") (name "ADC_T_JITTER_POT") (class "Default")
      (node (ref "C38") (pin "1") (pinfunction "1_1") (pintype "passive"))
      (node (ref "JP14") (pin "1") (pinfunction "1_1") (pintype "passive"))
      (node (ref "R37") (pin "2") (pinfunction "W_2") (pintype "passive"))
    )
    (net (code "7") (name "ADC_T_RATE_POT") (class "Default")
      (node (ref "C17") (pin "1") (pinfunction "1_1") (pintype "passive"))
      (node (ref "JP12") (pin "1") (pinfunction "1_1") (pintype "passive"))
      (node (ref "R13") (pin "2") (pinfunction "W_2") (pintype "passive"))
    )
    (net (code "8") (name "ADC_X_BIAS_POT") (class "Default")
      (node (ref "C29") (pin "1") (pinfunction "1_1") (pintype "passive"))
      (node (ref "JP18") (pin "1") (pinfunction "1_1") (pintype "passive"))
      (node (ref "R21") (pin "2") (pinfunction "W_2") (pintype "passive"))
    )
    (net (code "9") (name "ADC_X_SPREAD_POT") (class "Default")
      (node (ref "C18") (pin "1") (pinfunction "1_1") (pintype "passive"))
      (node (ref "JP17") (pin "1") (pinfunction "1_1") (pintype "passive"))
      (node (ref "R14") (pin "2") (pinfunction "W_2") (pintype "passive"))
    )
    (net (code "10") (name "ADC_X_STEPS_POT") (class "Default")
      (node (ref "C36") (pin "1") (pinfunction "1_1") (pintype "passive"))
      (node (ref "JP15") (pin "1") (pinfunction "1_1") (pintype "passive"))
      (node (ref "R38") (pin "2") (pinfunction "W_2") (pintype "passive"))
    )
    (net (code "11") (name "DAC_X_1") (class "Default")
      (node (ref "JP9") (pin "1") (pinfunction "1_1") (pintype "passive"))
      (node (ref "R47") (pin "2") (pinfunction "2_2") (pintype "passive"))
    )
    (net (code "12") (name "DAC_X_2") (class "Default")
      (node (ref "JP7") (pin "1") (pinfunction "1_1") (pintype "passive"))
      (node (ref "R48") (pin "2") (pinfunction "2_2") (pintype "passive"))
    )
    (net (code "13") (name "DAC_X_3") (class "Default")
      (node (ref "JP8") (pin "1") (pinfunction "1_1") (pintype "passive"))
      (node (ref "R53") (pin "2") (pinfunction "2_2") (pintype "passive"))
    )
    (net (code "14") (name "DAC_Y") (class "Default")
      (node (ref "JP10") (pin "1") (pinfunction "1_1") (pintype "passive"))
      (node (ref "R54") (pin "2") (pinfunction "2_2") (pintype "passive"))
    )
    (net (code "15") (name "GATE_T_1") (class "Default")
      (node (ref "JP3") (pin "1") (pinfunction "1_1") (pintype "passive"))
      (node (ref "L7") (pin "A") (pinfunction "A_A") (pintype "passive"))
      (node (ref "R56") (pin "2") (pinfunction "2_2") (pintype "passive"))
    )
    (net (code "16") (name "GATE_T_2") (class "Default")
      (node (ref "JP5") (pin "1") (pinfunction "1_1") (pintype "passive"))
      (node (ref "L8") (pin "A") (pinfunction "A_A") (pintype "passive"))
      (node (ref "R55") (pin "2") (pinfunction "2_2") (pintype "passive"))
    )
    (net (code "17") (name "GATE_T_3") (class "Default")
      (node (ref "JP6") (pin "1") (pinfunction "1_1") (pintype "passive"))
      (node (ref "L9") (pin "A") (pinfunction "A_A") (pintype "passive"))
      (node (ref "R67") (pin "2") (pinfunction "2_2") (pintype "passive"))
    )
    (net (code "18") (name "GND") (class "Default")
      (node (ref "C17") (pin "2") (pinfunction "2_2") (pintype "passive"))
      (node (ref "C18") (pin "2") (pinfunction "2_2") (pintype "passive"))
      (node (ref "C24") (pin "2") (pinfunction "2_2") (pintype "passive"))
      (node (ref "C28") (pin "2") (pinfunction "2_2") (pintype "passive"))
      (node (ref "C29") (pin "2") (pinfunction "2_2") (pintype "passive"))
      (node (ref "C36") (pin "2") (pinfunction "2_2") (pintype "passive"))
      (node (ref "C37") (pin "1") (pinfunction "1_1") (pintype "passive"))
      (node (ref "C38") (pin "2") (pinfunction "2_2") (pintype "passive"))
      (node (ref "C39") (pin "2") (pinfunction "2_2") (pintype "passive"))
      (node (ref "C45") (pin "2") (pinfunction "2_2") (pintype "passive"))
      (node (ref "C48") (pin "2") (pinfunction "2_2") (pintype "passive"))
      (node (ref "C49") (pin "1") (pinfunction "1_1") (pintype "passive"))
      (node (ref "C50") (pin "2") (pinfunction "2_2") (pintype "passive"))
      (node (ref "C51") (pin "2") (pinfunction "2_2") (pintype "passive"))
      (node (ref "C53") (pin "2") (pinfunction "2_2") (pintype "passive"))
      (node (ref "C54") (pin "2") (pinfunction "2_2") (pintype "passive"))
      (node (ref "C55") (pin "2") (pinfunction "2_2") (pintype "passive"))
      (node (ref "C56") (pin "2") (pinfunction "2_2") (pintype "passive"))
      (node (ref "C57") (pin "2") (pinfunction "2_2") (pintype "passive"))
      (node (ref "C58") (pin "2") (pinfunction "2_2") (pintype "passive"))
      (node (ref "C8") (pin "2") (pinfunction "2_2") (pintype "passive"))
      (node (ref "D3") (pin "1") (pinfunction "A_1") (pintype "passive"))
      (node (ref "D4") (pin "+") (pinfunction "+_+") (pintype "passive"))
      (node (ref "D5") (pin "+") (pinfunction "+_+") (pintype "passive"))
      (node (ref "IC9") (pin "11") (pinfunction "V-_11") (pintype "power_in"))
      (node (ref "IC9") (pin "5") (pinfunction "+IN_5") (pintype "input"))
      (node (ref "J1") (pin "GND") (pinfunction "GND_GND") (pintype "passive"))
      (node (ref "J1") (pin "NORM") (pinfunction "NORM_NORM") (pintype "passive"))
      (node (ref "J10") (pin "GND") (pinfunction "GND_GND") (pintype "passive"))
      (node (ref "J11") (pin "GND") (pinfunction "GND_GND") (pintype "passive"))
      (node (ref "J12") (pin "GND") (pinfunction "GND_GND") (pintype "passive"))
      (node (ref "J13") (pin "GND") (pinfunction "GND_GND") (pintype "passive"))
      (node (ref "J14") (pin "GND") (pinfunction "GND_GND") (pintype "passive"))
      (node (ref "J15") (pin "GND") (pinfunction "GND_GND") (pintype "passive"))
      (node (ref "J16") (pin "C") (pinfunction "C_C") (pintype "passive"))
      (node (ref "J16") (pin "GND") (pinfunction "GND_GND") (pintype "passive"))
      (node (ref "J2") (pin "C") (pinfunction "C_C") (pintype "passive"))
      (node (ref "J2") (pin "GND") (pinfunction "GND_GND") (pintype "passive"))
      (node (ref "J2") (pin "NORM") (pinfunction "NORM_NORM") (pintype "passive"))
      (node (ref "J3") (pin "GND") (pinfunction "GND_GND") (pintype "passive"))
      (node (ref "J4") (pin "GND") (pinfunction "GND_GND") (pintype "passive"))
      (node (ref "J4") (pin "NORM") (pinfunction "NORM_NORM") (pintype "passive"))
      (node (ref "J5") (pin "GND") (pinfunction "GND_GND") (pintype "passive"))
      (node (ref "J5") (pin "NORM") (pinfunction "NORM_NORM") (pintype "passive"))
      (node (ref "J6") (pin "GND") (pinfunction "GND_GND") (pintype "passive"))
      (node (ref "J6") (pin "NORM") (pinfunction "NORM_NORM") (pintype "passive"))
      (node (ref "J7") (pin "C") (pinfunction "C_C") (pintype "passive"))
      (node (ref "J7") (pin "GND") (pinfunction "GND_GND") (pintype "passive"))
      (node (ref "J7") (pin "NORM") (pinfunction "NORM_NORM") (pintype "passive"))
      (node (ref "J8") (pin "C") (pinfunction "C_C") (pintype "passive"))
      (node (ref "J8") (pin "GND") (pinfunction "GND_GND") (pintype "passive"))
      (node (ref "J8") (pin "NORM") (pinfunction "NORM_NORM") (pintype "passive"))
      (node (ref "J9") (pin "GND") (pinfunction "GND_GND") (pintype "passive"))
      (node (ref "JP105") (pin "1") (pinfunction "1_1") (pintype "passive"))
      (node (ref "JP106") (pin "1") (pinfunction "1_1") (pintype "passive"))
      (node (ref "JP108") (pin "1") (pinfunction "1_1") (pintype "passive"))
      (node (ref "JP109") (pin "1") (pinfunction "1_1") (pintype "passive"))
      (node (ref "L5") (pin "K") (pinfunction "C_K") (pintype "passive"))
      (node (ref "L6") (pin "K") (pinfunction "C_K") (pintype "passive"))
      (node (ref "LED1") (pin "2") (pinfunction "C_2") (pintype "bidirectional"))
      (node (ref "LED2") (pin "2") (pinfunction "C_2") (pintype "bidirectional"))
      (node (ref "LED3") (pin "2") (pinfunction "C_2") (pintype "bidirectional"))
      (node (ref "LED4") (pin "2") (pinfunction "C_2") (pintype "bidirectional"))
      (node (ref "LED5") (pin "2") (pinfunction "C_2") (pintype "bidirectional"))
      (node (ref "Q2") (pin "2") (pinfunction "E_2") (pintype "passive"))
      (node (ref "Q3") (pin "2") (pinfunction "E_2") (pintype "passive"))
      (node (ref "R13") (pin "1") (pinfunction "A_1") (pintype "passive"))
      (node (ref "R14") (pin "1") (pinfunction "A_1") (pintype "passive"))
      (node (ref "R16") (pin "1") (pinfunction "A_1") (pintype "passive"))
      (node (ref "R20") (pin "1") (pinfunction "A_1") (pintype "passive"))
      (node (ref "R21") (pin "1") (pinfunction "A_1") (pintype "passive"))
      (node (ref "R24") (pin "1") (pinfunction "1_1") (pintype "passive"))
      (node (ref "R25") (pin "1") (pinfunction "1_1") (pintype "passive"))
      (node (ref "R37") (pin "1") (pinfunction "A_1") (pintype "passive"))
      (node (ref "R38") (pin "1") (pinfunction "A_1") (pintype "passive"))
      (node (ref "R4") (pin "1") (pinfunction "A_1") (pintype "passive"))
      (node (ref "R49") (pin "2") (pinfunction "2_2") (pintype "passive"))
      (node (ref "R50") (pin "2") (pinfunction "2_2") (pintype "passive"))
      (node (ref "R73") (pin "1") (pinfunction "1_1") (pintype "passive"))
      (node (ref "R75") (pin "2") (pinfunction "2_2") (pintype "passive"))
      (node (ref "R78") (pin "2") (pinfunction "2_2") (pintype "passive"))
      (node (ref "R79") (pin "2") (pinfunction "2_2") (pintype "passive"))
      (node (ref "R80") (pin "2") (pinfunction "2_2") (pintype "passive"))
      (node (ref "R81") (pin "2") (pinfunction "2_2") (pintype "passive"))
      (node (ref "R82") (pin "1") (pinfunction "1_1") (pintype "passive"))
      (node (ref "R83") (pin "1") (pinfunction "1_1") (pintype "passive"))
      (node (ref "R84") (pin "1") (pinfunction "1_1") (pintype "passive"))
      (node (ref "SW1") (pin "3") (pinfunction "3_3") (pintype "passive"))
      (node (ref "SW1") (pin "4") (pinfunction "4_4") (pintype "passive"))
      (node (ref "SW2") (pin "3") (pinfunction "3_3") (pintype "passive"))
      (node (ref "SW2") (pin "4") (pinfunction "4_4") (pintype "passive"))
      (node (ref "SW3") (pin "1") (pinfunction "1_1") (pintype "passive"))
      (node (ref "SW3") (pin "2") (pinfunction "2_2") (pintype "passive"))
      (node (ref "SW4") (pin "1") (pinfunction "1_1") (pintype "passive"))
      (node (ref "SW4") (pin "2") (pinfunction "2_2") (pintype "passive"))
      (node (ref "SW5") (pin "1") (pinfunction "1_1") (pintype "passive"))
      (node (ref "SW5") (pin "2") (pinfunction "2_2") (pintype "passive"))
      (node (ref "SW6") (pin "1") (pinfunction "1_1") (pintype "passive"))
      (node (ref "SW6") (pin "2") (pinfunction "2_2") (pintype "passive"))
      (node (ref "SW7") (pin "1") (pinfunction "1_1") (pintype "passive"))
      (node (ref "SW7") (pin "2") (pinfunction "2_2") (pintype "passive"))
    )
    (net (code "19") (name "LED_T_DV") (class "Default")
      (node (ref "JP27") (pin "1") (pinfunction "1_1") (pintype "passive"))
      (node (ref "R1") (pin "1") (pinfunction "1_1") (pintype "passive"))
    )
    (net (code "20") (name "LED_T_MODE_G") (class "Default")
      (node (ref "JP32") (pin "1") (pinfunction "1_1") (pintype "passive"))
      (node (ref "R10") (pin "1") (pinfunction "1_1") (pintype "passive"))
    )
    (net (code "21") (name "LED_T_MODE_R") (class "Default")
      (node (ref "JP31") (pin "1") (pinfunction "1_1") (pintype "passive"))
      (node (ref "R9") (pin "1") (pinfunction "1_1") (pintype "passive"))
    )
    (net (code "22") (name "LED_T_RANGE_G") (class "Default")
      (node (ref "JP30") (pin "1") (pinfunction "1_1") (pintype "passive"))
      (node (ref "R18") (pin "1") (pinfunction "1_1") (pintype "passive"))
    )
    (net (code "23") (name "LED_T_RANGE_R") (class "Default")
      (node (ref "JP29") (pin "1") (pinfunction "1_1") (pintype "passive"))
      (node (ref "R19") (pin "1") (pinfunction "1_1") (pintype "passive"))
    )
    (net (code "24") (name "LED_X_DV") (class "Default")
      (node (ref "JP25") (pin "1") (pinfunction "1_1") (pintype "passive"))
      (node (ref "R5") (pin "1") (pinfunction "1_1") (pintype "passive"))
    )
    (net (code "25") (name "LED_X_EXT_G") (class "Default")
      (node (ref "JP28") (pin "1") (pinfunction "1_1") (pintype "passive"))
      (node (ref "R36") (pin "1") (pinfunction "1_1") (pintype "passive"))
    )
    (net (code "26") (name "LED_X_MODE_G") (class "Default")
      (node (ref "JP34") (pin "1") (pinfunction "1_1") (pintype "passive"))
      (node (ref "R12") (pin "1") (pinfunction "1_1") (pintype "passive"))
    )
    (net (code "27") (name "LED_X_MODE_R") (class "Default")
      (node (ref "JP33") (pin "1") (pinfunction "1_1") (pintype "passive"))
      (node (ref "R11") (pin "1") (pinfunction "1_1") (pintype "passive"))
    )
    (net (code "28") (name "LED_X_RANGE_G") (class "Default")
      (node (ref "JP36") (pin "1") (pinfunction "1_1") (pintype "passive"))
      (node (ref "R17") (pin "1") (pinfunction "1_1") (pintype "passive"))
    )
    (net (code "29") (name "LED_X_RANGE_R") (class "Default")
      (node (ref "JP35") (pin "1") (pinfunction "1_1") (pintype "passive"))
      (node (ref "R15") (pin "1") (pinfunction "1_1") (pintype "passive"))
    )
    (net (code "30") (name "L_DV_CV") (class "Default")
      (node (ref "JP62") (pin "1") (pinfunction "1_1") (pintype "passive"))
      (node (ref "R32") (pin "1") (pinfunction "1_1") (pintype "passive"))
    )
    (net (code "31") (name "L_T_BIAS_CV") (class "Default")
      (node (ref "JP46") (pin "1") (pinfunction "1_1") (pintype "passive"))
      (node (ref "R64") (pin "1") (pinfunction "1_1") (pintype "passive"))
    )
    (net (code "32") (name "L_T_JITTER_CV") (class "Default")
      (node (ref "JP51") (pin "1") (pinfunction "1_1") (pintype "passive"))
      (node (ref "R66") (pin "1") (pinfunction "1_1") (pintype "passive"))
    )
    (net (code "33") (name "L_T_RATE_CV") (class "Default")
      (node (ref "JP48") (pin "1") (pinfunction "1_1") (pintype "passive"))
      (node (ref "R65") (pin "1") (pinfunction "1_1") (pintype "passive"))
    )
    (net (code "34") (name "L_X_BIAS_CV") (class "Default")
      (node (ref "JP60") (pin "1") (pinfunction "1_1") (pintype "passive"))
      (node (ref "R33") (pin "1") (pinfunction "1_1") (pintype "passive"))
    )
    (net (code "35") (name "L_X_SPREAD_CV") (class "Default")
      (node (ref "JP58") (pin "1") (pinfunction "1_1") (pintype "passive"))
      (node (ref "R34") (pin "1") (pinfunction "1_1") (pintype "passive"))
    )
    (net (code "36") (name "NORMALIZATION_PROBE") (class "Default")
      (node (ref "D3") (pin "3") (pinfunction "AC_3") (pintype "passive"))
      (node (ref "JP43") (pin "1") (pinfunction "1_1") (pintype "passive"))
      (node (ref "R76") (pin "1") (pinfunction "1_1") (pintype "passive"))
      (node (ref "R77") (pin "1") (pinfunction "1_1") (pintype "passive"))
    )
    (net (code "37") (name "Net-(C45-Pad1)") (class "Default")
      (node (ref "C45") (pin "1") (pinfunction "1_1") (pintype "passive"))
      (node (ref "J2") (pin "IN") (pinfunction "IN_IN") (pintype "passive"))
      (node (ref "R33") (pin "2") (pinfunction "2_2") (pintype "passive"))
    )
    (net (code "38") (name "Net-(C53-Pad1)") (class "Default")
      (node (ref "C53") (pin "1") (pinfunction "1_1") (pintype "passive"))
      (node (ref "J1") (pin "IN") (pinfunction "IN_IN") (pintype "passive"))
      (node (ref "R64") (pin "2") (pinfunction "2_2") (pintype "passive"))
    )
    (net (code "39") (name "Net-(C54-Pad1)") (class "Default")
      (node (ref "C54") (pin "1") (pinfunction "1_1") (pintype "passive"))
      (node (ref "J6") (pin "IN") (pinfunction "IN_IN") (pintype "passive"))
      (node (ref "R32") (pin "2") (pinfunction "2_2") (pintype "passive"))
    )
    (net (code "40") (name "Net-(C55-Pad1)") (class "Default")
      (node (ref "C55") (pin "1") (pinfunction "1_1") (pintype "passive"))
      (node (ref "J7") (pin "IN") (pinfunction "IN_IN") (pintype "passive"))
      (node (ref "R35") (pin "2") (pinfunction "2_2") (pintype "passive"))
    )
    (net (code "41") (name "Net-(C56-Pad1)") (class "Default")
      (node (ref "C56") (pin "1") (pinfunction "1_1") (pintype "passive"))
      (node (ref "J4") (pin "IN") (pinfunction "IN_IN") (pintype "passive"))
      (node (ref "R65") (pin "2") (pinfunction "2_2") (pintype "passive"))
    )
    (net (code "42") (name "Net-(C57-Pad1)") (class "Default")
      (node (ref "C57") (pin "1") (pinfunction "1_1") (pintype "passive"))
      (node (ref "J8") (pin "IN") (pinfunction "IN_IN") (pintype "passive"))
      (node (ref "R34") (pin "2") (pinfunction "2_2") (pintype "passive"))
    )
    (net (code "43") (name "Net-(C58-Pad1)") (class "Default")
      (node (ref "C58") (pin "1") (pinfunction "1_1") (pintype "passive"))
      (node (ref "J5") (pin "IN") (pinfunction "IN_IN") (pintype "passive"))
      (node (ref "R66") (pin "2") (pinfunction "2_2") (pintype "passive"))
    )
    (net (code "44") (name "Net-(IC7A--IN)") (class "Default")
      (node (ref "C44") (pin "1") (pinfunction "1_1") (pintype "passive"))
      (node (ref "IC7") (pin "2") (pinfunction "-IN_2") (pintype "input"))
      (node (ref "R53") (pin "1") (pinfunction "1_1") (pintype "passive"))
      (node (ref "R61") (pin "2") (pinfunction "2_2") (pintype "passive"))
    )
    (net (code "45") (name "Net-(IC7B--IN)") (class "Default")
      (node (ref "C43") (pin "1") (pinfunction "1_1") (pintype "passive"))
      (node (ref "IC7") (pin "6") (pinfunction "-IN_6") (pintype "input"))
      (node (ref "R54") (pin "1") (pinfunction "1_1") (pintype "passive"))
      (node (ref "R60") (pin "2") (pinfunction "2_2") (pintype "passive"))
    )
    (net (code "46") (name "Net-(IC7C--IN)") (class "Default")
      (node (ref "C35") (pin "1") (pinfunction "1_1") (pintype "passive"))
      (node (ref "IC7") (pin "9") (pinfunction "-IN_9") (pintype "input"))
      (node (ref "R44") (pin "2") (pinfunction "2_2") (pintype "passive"))
      (node (ref "R48") (pin "1") (pinfunction "1_1") (pintype "passive"))
    )
    (net (code "47") (name "Net-(IC7D--IN)") (class "Default")
      (node (ref "C34") (pin "1") (pinfunction "1_1") (pintype "passive"))
      (node (ref "IC7") (pin "13") (pinfunction "-IN_13") (pintype "input"))
      (node (ref "R43") (pin "2") (pinfunction "2_2") (pintype "passive"))
      (node (ref "R47") (pin "1") (pinfunction "1_1") (pintype "passive"))
    )
    (net (code "48") (name "Net-(IC9A-+IN)") (class "Default")
      (node (ref "IC9") (pin "3") (pinfunction "+IN_3") (pintype "input"))
      (node (ref "R67") (pin "1") (pinfunction "1_1") (pintype "passive"))
    )
    (net (code "49") (name "Net-(IC9A--IN)") (class "Default")
      (node (ref "IC9") (pin "2") (pinfunction "-IN_2") (pintype "input"))
      (node (ref "R69") (pin "2") (pinfunction "2_2") (pintype "passive"))
      (node (ref "R75") (pin "1") (pinfunction "1_1") (pintype "passive"))
    )
    (net (code "50") (name "Net-(IC9A-OUT)") (class "Default")
      (node (ref "IC9") (pin "1") (pinfunction "OUT_1") (pintype "output"))
      (node (ref "R69") (pin "1") (pinfunction "1_1") (pintype "passive"))
      (node (ref "R87") (pin "2") (pinfunction "2_2") (pintype "passive"))
    )
    (net (code "51") (name "Net-(IC9B--IN)") (class "Default")
      (node (ref "IC9") (pin "6") (pinfunction "-IN_6") (pintype "input"))
      (node (ref "IC9") (pin "7") (pinfunction "OUT_7") (pintype "output"))
    )
    (net (code "52") (name "Net-(IC9C-+IN)") (class "Default")
      (node (ref "IC9") (pin "10") (pinfunction "+IN_10") (pintype "input"))
      (node (ref "R56") (pin "1") (pinfunction "1_1") (pintype "passive"))
    )
    (net (code "53") (name "Net-(IC9C--IN)") (class "Default")
      (node (ref "IC9") (pin "9") (pinfunction "-IN_9") (pintype "input"))
      (node (ref "R50") (pin "1") (pinfunction "1_1") (pintype "passive"))
      (node (ref "R51") (pin "2") (pinfunction "2_2") (pintype "passive"))
    )
    (net (code "54") (name "Net-(IC9C-OUT)") (class "Default")
      (node (ref "IC9") (pin "8") (pinfunction "OUT_8") (pintype "output"))
      (node (ref "R51") (pin "1") (pinfunction "1_1") (pintype "passive"))
      (node (ref "R85") (pin "2") (pinfunction "2_2") (pintype "passive"))
    )
    (net (code "55") (name "Net-(IC9D-+IN)") (class "Default")
      (node (ref "IC9") (pin "12") (pinfunction "+IN_12") (pintype "input"))
      (node (ref "R55") (pin "1") (pinfunction "1_1") (pintype "passive"))
    )
    (net (code "56") (name "Net-(IC9D--IN)") (class "Default")
      (node (ref "IC9") (pin "13") (pinfunction "-IN_13") (pintype "input"))
      (node (ref "R49") (pin "1") (pinfunction "1_1") (pintype "passive"))
      (node (ref "R52") (pin "2") (pinfunction "2_2") (pintype "passive"))
    )
    (net (code "57") (name "Net-(IC9D-OUT)") (class "Default")
      (node (ref "IC9") (pin "14") (pinfunction "OUT_14") (pintype "output"))
      (node (ref "R52") (pin "1") (pinfunction "1_1") (pintype "passive"))
      (node (ref "R86") (pin "2") (pinfunction "2_2") (pintype "passive"))
    )
    (net (code "58") (name "Net-(IC10A-+IN)") (class "Default")
      (node (ref "C34") (pin "2") (pinfunction "2_2") (pintype "passive"))
      (node (ref "IC10") (pin "3") (pinfunction "+IN_3") (pintype "input"))
      (node (ref "IC7") (pin "14") (pinfunction "OUT_14") (pintype "output"))
      (node (ref "R45") (pin "2") (pinfunction "2_2") (pintype "passive"))
    )
    (net (code "59") (name "Net-(IC10A--IN)") (class "Default")
      (node (ref "IC10") (pin "2") (pinfunction "-IN_2") (pintype "input"))
      (node (ref "L12") (pin "K") (pinfunction "C_K") (pintype "passive"))
      (node (ref "R79") (pin "1") (pinfunction "1_1") (pintype "passive"))
    )
    (net (code "60") (name "Net-(IC10A-OUT)") (class "Default")
      (node (ref "IC10") (pin "1") (pinfunction "OUT_1") (pintype "output"))
      (node (ref "L12") (pin "A") (pinfunction "A_A") (pintype "passive"))
    )
    (net (code "61") (name "Net-(IC10B-+IN)") (class "Default")
      (node (ref "C43") (pin "2") (pinfunction "2_2") (pintype "passive"))
      (node (ref "IC10") (pin "5") (pinfunction "+IN_5") (pintype "input"))
      (node (ref "IC7") (pin "7") (pinfunction "OUT_7") (pintype "output"))
      (node (ref "R62") (pin "2") (pinfunction "2_2") (pintype "passive"))
    )
    (net (code "62") (name "Net-(IC10B--IN)") (class "Default")
      (node (ref "IC10") (pin "6") (pinfunction "-IN_6") (pintype "input"))
      (node (ref "L13") (pin "K") (pinfunction "C_K") (pintype "passive"))
      (node (ref "R78") (pin "1") (pinfunction "1_1") (pintype "passive"))
    )
    (net (code "63") (name "Net-(IC10B-OUT)") (class "Default")
      (node (ref "IC10") (pin "7") (pinfunction "OUT_7") (pintype "output"))
      (node (ref "L13") (pin "A") (pinfunction "A_A") (pintype "passive"))
    )
    (net (code "64") (name "Net-(IC10C-+IN)") (class "Default")
      (node (ref "C44") (pin "2") (pinfunction "2_2") (pintype "passive"))
      (node (ref "IC10") (pin "10") (pinfunction "+IN_10") (pintype "input"))
      (node (ref "IC7") (pin "1") (pinfunction "OUT_1") (pintype "output"))
      (node (ref "R63") (pin "2") (pinfunction "2_2") (pintype "passive"))
    )
    (net (code "65") (name "Net-(IC10C--IN)") (class "Default")
      (node (ref "IC10") (pin "9") (pinfunction "-IN_9") (pintype "input"))
      (node (ref "L11") (pin "K") (pinfunction "C_K") (pintype "passive"))
      (node (ref "R81") (pin "1") (pinfunction "1_1") (pintype "passive"))
    )
    (net (code "66") (name "Net-(IC10C-OUT)") (class "Default")
      (node (ref "IC10") (pin "8") (pinfunction "OUT_8") (pintype "output"))
      (node (ref "L11") (pin "A") (pinfunction "A_A") (pintype "passive"))
    )
    (net (code "67") (name "Net-(IC10D-+IN)") (class "Default")
      (node (ref "C35") (pin "2") (pinfunction "2_2") (pintype "passive"))
      (node (ref "IC10") (pin "12") (pinfunction "+IN_12") (pintype "input"))
      (node (ref "IC7") (pin "8") (pinfunction "OUT_8") (pintype "output"))
      (node (ref "R46") (pin "2") (pinfunction "2_2") (pintype "passive"))
    )
    (net (code "68") (name "Net-(IC10D--IN)") (class "Default")
      (node (ref "IC10") (pin "13") (pinfunction "-IN_13") (pintype "input"))
      (node (ref "L10") (pin "K") (pinfunction "C_K") (pintype "passive"))
      (node (ref "R80") (pin "1") (pinfunction "1_1") (pintype "passive"))
    )
    (net (code "69") (name "Net-(IC10D-OUT)") (class "Default")
      (node (ref "IC10") (pin "14") (pinfunction "OUT_14") (pintype "output"))
      (node (ref "L10") (pin "A") (pinfunction "A_A") (pintype "passive"))
    )
    (net (code "70") (name "Net-(J1-PadA)") (class "Default")
      (node (ref "J1") (pin "A") (pinfunction "A_A") (pintype "passive"))
      (node (ref "J11") (pin "C") (pinfunction "C_C") (pintype "passive"))
    )
    (net (code "71") (name "Net-(J1-PadC)") (class "Default")
      (node (ref "J1") (pin "C") (pinfunction "C_C") (pintype "passive"))
      (node (ref "J9") (pin "A") (pinfunction "A_A") (pintype "passive"))
    )
    (net (code "72") (name "Net-(J2-PadA)") (class "Default")
      (node (ref "J2") (pin "A") (pinfunction "A_A") (pintype "passive"))
      (node (ref "J9") (pin "C") (pinfunction "C_C") (pintype "passive"))
    )
    (net (code "73") (name "Net-(J3-PadA)") (class "Default")
      (node (ref "J3") (pin "A") (pinfunction "A_A") (pintype "passive"))
      (node (ref "J4") (pin "C") (pinfunction "C_C") (pintype "passive"))
    )
    (net (code "74") (name "Net-(J3-PadC)") (class "Default")
      (node (ref "J3") (pin "C") (pinfunction "C_C") (pintype "passive"))
      (node (ref "J8") (pin "A") (pinfunction "A_A") (pintype "passive"))
    )
    (net (code "75") (name "Net-(J3-PadIN)") (class "Default")
      (node (ref "J3") (pin "IN") (pinfunction "IN_IN") (pintype "passive"))
      (node (ref "R26") (pin "1") (pinfunction "1_1") (pintype "passive"))
    )
    (net (code "76") (name "Net-(J3-PadNORM)") (class "Default")
      (node (ref "J3") (pin "NORM") (pinfunction "NORM_NORM") (pintype "passive"))
      (node (ref "R76") (pin "2") (pinfunction "2_2") (pintype "passive"))
    )
    (net (code "77") (name "Net-(J6-PadA)") (class "Default")
      (node (ref "J6") (pin "A") (pinfunction "A_A") (pintype "passive"))
      (node (ref "R7") (pin "2") (pinfunction "2_2") (pintype "passive"))
    )
    (net (code "78") (name "Net-(J9-PadIN)") (class "Default")
      (node (ref "J9") (pin "IN") (pinfunction "IN_IN") (pintype "passive"))
      (node (ref "R27") (pin "1") (pinfunction "1_1") (pintype "passive"))
    )
    (net (code "79") (name "Net-(J9-PadNORM)") (class "Default")
      (node (ref "J9") (pin "NORM") (pinfunction "NORM_NORM") (pintype "passive"))
      (node (ref "R77") (pin "2") (pinfunction "2_2") (pintype "passive"))
    )
    (net (code "80") (name "Net-(J10-PadA)") (class "Default")
      (node (ref "J10") (pin "A") (pinfunction "A_A") (pintype "passive"))
      (node (ref "R2") (pin "2") (pinfunction "2_2") (pintype "passive"))
    )
    (net (code "81") (name "Net-(J10-PadC)") (class "Default")
      (node (ref "J10") (pin "C") (pinfunction "C_C") (pintype "passive"))
      (node (ref "J4") (pin "A") (pinfunction "A_A") (pintype "passive"))
    )
    (net (code "82") (name "Net-(J10-PadIN)") (class "Default")
      (node (ref "J10") (pin "IN") (pinfunction "IN_IN") (pintype "passive"))
      (node (ref "R85") (pin "1") (pinfunction "1_1") (pintype "passive"))
    )
    (net (code "83") (name "Net-(J11-PadA)") (class "Default")
      (node (ref "J11") (pin "A") (pinfunction "A_A") (pintype "passive"))
      (node (ref "R3") (pin "2") (pinfunction "2_2") (pintype "passive"))
    )
    (net (code "84") (name "Net-(J11-PadIN)") (class "Default")
      (node (ref "J11") (pin "IN") (pinfunction "IN_IN") (pintype "passive"))
      (node (ref "R86") (pin "1") (pinfunction "1_1") (pintype "passive"))
    )
    (net (code "85") (name "Net-(J12-PadA)") (class "Default")
      (node (ref "J12") (pin "A") (pinfunction "A_A") (pintype "passive"))
      (node (ref "R6") (pin "2") (pinfunction "2_2") (pintype "passive"))
    )
    (net (code "86") (name "Net-(J12-PadC)") (class "Default")
      (node (ref "J12") (pin "C") (pinfunction "C_C") (pintype "passive"))
      (node (ref "J5") (pin "A") (pinfunction "A_A") (pintype "passive"))
    )
    (net (code "87") (name "Net-(J12-PadIN)") (class "Default")
      (node (ref "J12") (pin "IN") (pinfunction "IN_IN") (pintype "passive"))
      (node (ref "R87") (pin "1") (pinfunction "1_1") (pintype "passive"))
    )
    (net (code "88") (name "Net-(J13-PadA)") (class "Default")
      (node (ref "J13") (pin "A") (pinfunction "A_A") (pintype "passive"))
      (node (ref "J5") (pin "C") (pinfunction "C_C") (pintype "passive"))
    )
    (net (code "89") (name "Net-(J13-PadC)") (class "Default")
      (node (ref "J13") (pin "C") (pinfunction "C_C") (pintype "passive"))
      (node (ref "J7") (pin "A") (pinfunction "A_A") (pintype "passive"))
    )
    (net (code "90") (name "Net-(J13-PadIN)") (class "Default")
      (node (ref "J13") (pin "IN") (pinfunction "IN_IN") (pintype "passive"))
      (node (ref "R60") (pin "1") (pinfunction "1_1") (pintype "passive"))
      (node (ref "R62") (pin "1") (pinfunction "1_1") (pintype "passive"))
    )
    (net (code "91") (name "Net-(J14-PadA)") (class "Default")
      (node (ref "J14") (pin "A") (pinfunction "A_A") (pintype "passive"))
      (node (ref "J6") (pin "C") (pinfunction "C_C") (pintype "passive"))
    )
    (net (code "92") (name "Net-(J14-PadC)") (class "Default")
      (node (ref "J14") (pin "C") (pinfunction "C_C") (pintype "passive"))
      (node (ref "J15") (pin "A") (pinfunction "A_A") (pintype "passive"))
    )
    (net (code "93") (name "Net-(J14-PadIN)") (class "Default")
      (node (ref "J14") (pin "IN") (pinfunction "IN_IN") (pintype "passive"))
      (node (ref "R43") (pin "1") (pinfunction "1_1") (pintype "passive"))
      (node (ref "R45") (pin "1") (pinfunction "1_1") (pintype "passive"))
    )
    (net (code "94") (name "Net-(J15-PadC)") (class "Default")
      (node (ref "J15") (pin "C") (pinfunction "C_C") (pintype "passive"))
      (node (ref "J16") (pin "A") (pinfunction "A_A") (pintype "passive"))
    )
    (net (code "95") (name "Net-(J15-PadIN)") (class "Default")
      (node (ref "J15") (pin "IN") (pinfunction "IN_IN") (pintype "passive"))
      (node (ref "R44") (pin "1") (pinfunction "1_1") (pintype "passive"))
      (node (ref "R46") (pin "1") (pinfunction "1_1") (pintype "passive"))
    )
    (net (code "96") (name "Net-(J16-PadIN)") (class "Default")
      (node (ref "J16") (pin "IN") (pinfunction "IN_IN") (pintype "passive"))
      (node (ref "R61") (pin "1") (pinfunction "1_1") (pintype "passive"))
      (node (ref "R63") (pin "1") (pinfunction "1_1") (pintype "passive"))
    )
    (net (code "97") (name "Net-(JP47-Pad1)") (class "Default")
      (node (ref "JP47") (pin "1") (pinfunction "1_1") (pintype "passive"))
      (node (ref "R35") (pin "1") (pinfunction "1_1") (pintype "passive"))
    )
    (net (code "98") (name "Net-(JP107-Pad1)") (class "Default")
      (node (ref "JP107") (pin "1") (pinfunction "1_1") (pintype "passive"))
      (node (ref "R2") (pin "1") (pinfunction "1_1") (pintype "passive"))
      (node (ref "R3") (pin "1") (pinfunction "1_1") (pintype "passive"))
      (node (ref "R6") (pin "1") (pinfunction "1_1") (pintype "passive"))
      (node (ref "R7") (pin "1") (pinfunction "1_1") (pintype "passive"))
    )
    (net (code "99") (name "Net-(L5-PadA)") (class "Default")
      (node (ref "L5") (pin "A") (pinfunction "A_A") (pintype "passive"))
      (node (ref "R1") (pin "2") (pinfunction "2_2") (pintype "passive"))
    )
    (net (code "100") (name "Net-(L6-PadA)") (class "Default")
      (node (ref "L6") (pin "A") (pinfunction "A_A") (pintype "passive"))
      (node (ref "R5") (pin "2") (pinfunction "2_2") (pintype "passive"))
    )
    (net (code "101") (name "Net-(L7-C)") (class "Default")
      (node (ref "L7") (pin "K") (pinfunction "C_K") (pintype "passive"))
      (node (ref "R82") (pin "2") (pinfunction "2_2") (pintype "passive"))
    )
    (net (code "102") (name "Net-(L8-C)") (class "Default")
      (node (ref "L8") (pin "K") (pinfunction "C_K") (pintype "passive"))
      (node (ref "R83") (pin "2") (pinfunction "2_2") (pintype "passive"))
    )
    (net (code "103") (name "Net-(L9-C)") (class "Default")
      (node (ref "L9") (pin "K") (pinfunction "C_K") (pintype "passive"))
      (node (ref "R84") (pin "2") (pinfunction "2_2") (pintype "passive"))
    )
    (net (code "104") (name "Net-(LED1-GRN)") (class "Default")
      (node (ref "LED1") (pin "1") (pinfunction "GRN_1") (pintype "bidirectional"))
      (node (ref "R10") (pin "2") (pinfunction "2_2") (pintype "passive"))
    )
    (net (code "105") (name "Net-(LED1-RED)") (class "Default")
      (node (ref "LED1") (pin "3") (pinfunction "RED_3") (pintype "bidirectional"))
      (node (ref "R9") (pin "2") (pinfunction "2_2") (pintype "passive"))
    )
    (net (code "106") (name "Net-(LED2-GRN)") (class "Default")
      (node (ref "LED2") (pin "1") (pinfunction "GRN_1") (pintype "bidirectional"))
      (node (ref "R12") (pin "2") (pinfunction "2_2") (pintype "passive"))
    )
    (net (code "107") (name "Net-(LED2-RED)") (class "Default")
      (node (ref "LED2") (pin "3") (pinfunction "RED_3") (pintype "bidirectional"))
      (node (ref "R11") (pin "2") (pinfunction "2_2") (pintype "passive"))
    )
    (net (code "108") (name "Net-(LED3-GRN)") (class "Default")
      (node (ref "LED3") (pin "1") (pinfunction "GRN_1") (pintype "bidirectional"))
      (node (ref "R18") (pin "2") (pinfunction "2_2") (pintype "passive"))
    )
    (net (code "109") (name "Net-(LED3-RED)") (class "Default")
      (node (ref "LED3") (pin "3") (pinfunction "RED_3") (pintype "bidirectional"))
      (node (ref "R19") (pin "2") (pinfunction "2_2") (pintype "passive"))
    )
    (net (code "110") (name "Net-(LED4-GRN)") (class "Default")
      (node (ref "LED4") (pin "1") (pinfunction "GRN_1") (pintype "bidirectional"))
      (node (ref "R17") (pin "2") (pinfunction "2_2") (pintype "passive"))
    )
    (net (code "111") (name "Net-(LED4-RED)") (class "Default")
      (node (ref "LED4") (pin "3") (pinfunction "RED_3") (pintype "bidirectional"))
      (node (ref "R15") (pin "2") (pinfunction "2_2") (pintype "passive"))
    )
    (net (code "112") (name "Net-(LED5-GRN)") (class "Default")
      (node (ref "LED5") (pin "1") (pinfunction "GRN_1") (pintype "bidirectional"))
      (node (ref "R36") (pin "2") (pinfunction "2_2") (pintype "passive"))
    )
    (net (code "113") (name "Net-(Q2-B)") (class "Default")
      (node (ref "D4") (pin "-") (pinfunction "-_-") (pintype "passive"))
      (node (ref "Q2") (pin "1") (pinfunction "B_1") (pintype "passive"))
      (node (ref "R24") (pin "2") (pinfunction "2_2") (pintype "passive"))
      (node (ref "R26") (pin "2") (pinfunction "2_2") (pintype "passive"))
    )
    (net (code "114") (name "Net-(Q3-B)") (class "Default")
      (node (ref "D5") (pin "-") (pinfunction "-_-") (pintype "passive"))
      (node (ref "Q3") (pin "1") (pinfunction "B_1") (pintype "passive"))
      (node (ref "R25") (pin "2") (pinfunction "2_2") (pintype "passive"))
      (node (ref "R27") (pin "2") (pinfunction "2_2") (pintype "passive"))
    )
    (net (code "115") (name "SW_T_DV") (class "Default")
      (node (ref "JP26") (pin "1") (pinfunction "1_1") (pintype "passive"))
      (node (ref "SW1") (pin "1") (pinfunction "1_1") (pintype "passive"))
      (node (ref "SW1") (pin "2") (pinfunction "2_2") (pintype "passive"))
    )
    (net (code "116") (name "SW_T_MODE") (class "Default")
      (node (ref "JP21") (pin "1") (pinfunction "1_1") (pintype "passive"))
      (node (ref "SW3") (pin "3") (pinfunction "3_3") (pintype "passive"))
      (node (ref "SW3") (pin "4") (pinfunction "4_4") (pintype "passive"))
    )
    (net (code "117") (name "SW_T_RANGE") (class "Default")
      (node (ref "JP20") (pin "1") (pinfunction "1_1") (pintype "passive"))
      (node (ref "SW5") (pin "3") (pinfunction "3_3") (pintype "passive"))
      (node (ref "SW5") (pin "4") (pinfunction "4_4") (pintype "passive"))
    )
    (net (code "118") (name "SW_X_DV") (class "Default")
      (node (ref "JP24") (pin "1") (pinfunction "1_1") (pintype "passive"))
      (node (ref "SW2") (pin "1") (pinfunction "1_1") (pintype "passive"))
      (node (ref "SW2") (pin "2") (pinfunction "2_2") (pintype "passive"))
    )
    (net (code "119") (name "SW_X_EXT") (class "Default")
      (node (ref "JP19") (pin "1") (pinfunction "1_1") (pintype "passive"))
      (node (ref "SW7") (pin "3") (pinfunction "3_3") (pintype "passive"))
      (node (ref "SW7") (pin "4") (pinfunction "4_4") (pintype "passive"))
    )
    (net (code "120") (name "SW_X_MODE") (class "Default")
      (node (ref "JP22") (pin "1") (pinfunction "1_1") (pintype "passive"))
      (node (ref "SW4") (pin "3") (pinfunction "3_3") (pintype "passive"))
      (node (ref "SW4") (pin "4") (pinfunction "4_4") (pintype "passive"))
    )
    (net (code "121") (name "SW_X_RANGE") (class "Default")
      (node (ref "JP23") (pin "1") (pinfunction "1_1") (pintype "passive"))
      (node (ref "SW6") (pin "3") (pinfunction "3_3") (pintype "passive"))
      (node (ref "SW6") (pin "4") (pinfunction "4_4") (pintype "passive"))
    )
    (net (code "122") (name "T_CLOCK") (class "Default")
      (node (ref "JP45") (pin "1") (pinfunction "1_1") (pintype "passive"))
      (node (ref "Q2") (pin "3") (pinfunction "C_3") (pintype "passive"))
      (node (ref "R22") (pin "1") (pinfunction "1_1") (pintype "passive"))
    )
    (net (code "123") (name "VCC") (class "Default")
      (node (ref "C39") (pin "1") (pinfunction "1_1") (pintype "passive"))
      (node (ref "C48") (pin "1") (pinfunction "1_1") (pintype "passive"))
      (node (ref "C50") (pin "1") (pinfunction "1_1") (pintype "passive"))
      (node (ref "IC10") (pin "4") (pinfunction "V+_4") (pintype "power_in"))
      (node (ref "IC7") (pin "4") (pinfunction "V+_4") (pintype "power_in"))
      (node (ref "IC9") (pin "4") (pinfunction "V+_4") (pintype "power_in"))
      (node (ref "JP102") (pin "1") (pinfunction "1_1") (pintype "passive"))
    )
    (net (code "124") (name "VEE") (class "Default")
      (node (ref "C37") (pin "2") (pinfunction "2_2") (pintype "passive"))
      (node (ref "C49") (pin "2") (pinfunction "2_2") (pintype "passive"))
      (node (ref "IC10") (pin "11") (pinfunction "V-_11") (pintype "power_in"))
      (node (ref "IC7") (pin "11") (pinfunction "V-_11") (pintype "power_in"))
      (node (ref "JP103") (pin "1") (pinfunction "1_1") (pintype "passive"))
    )
    (net (code "125") (name "VREF") (class "Default")
      (node (ref "JP37") (pin "1") (pinfunction "1_1") (pintype "passive"))
      (node (ref "R74") (pin "2") (pinfunction "2_2") (pintype "passive"))
    )
    (net (code "126") (name "VREF_BIAS") (class "Default")
      (node (ref "C51") (pin "1") (pinfunction "1_1") (pintype "passive"))
      (node (ref "IC7") (pin "10") (pinfunction "+IN_10") (pintype "input"))
      (node (ref "IC7") (pin "12") (pinfunction "+IN_12") (pintype "input"))
      (node (ref "IC7") (pin "3") (pinfunction "+IN_3") (pintype "input"))
      (node (ref "IC7") (pin "5") (pinfunction "+IN_5") (pintype "input"))
      (node (ref "R73") (pin "2") (pinfunction "2_2") (pintype "passive"))
      (node (ref "R74") (pin "1") (pinfunction "1_1") (pintype "passive"))
    )
    (net (code "127") (name "X_CLOCK") (class "Default")
      (node (ref "JP44") (pin "1") (pinfunction "1_1") (pintype "passive"))
      (node (ref "Q3") (pin "3") (pinfunction "C_3") (pintype "passive"))
      (node (ref "R23") (pin "1") (pinfunction "1_1") (pintype "passive"))
    )
    (net (code "128") (name "unconnected-(J10-PadNORM)") (class "Default")
      (node (ref "J10") (pin "NORM") (pinfunction "NORM_NORM") (pintype "passive"))
    )
    (net (code "129") (name "unconnected-(J11-PadNORM)") (class "Default")
      (node (ref "J11") (pin "NORM") (pinfunction "NORM_NORM") (pintype "passive"))
    )
    (net (code "130") (name "unconnected-(J12-PadNORM)") (class "Default")
      (node (ref "J12") (pin "NORM") (pinfunction "NORM_NORM") (pintype "passive"))
    )
    (net (code "131") (name "unconnected-(J13-PadNORM)") (class "Default")
      (node (ref "J13") (pin "NORM") (pinfunction "NORM_NORM") (pintype "passive"))
    )
    (net (code "132") (name "unconnected-(J14-PadNORM)") (class "Default")
      (node (ref "J14") (pin "NORM") (pinfunction "NORM_NORM") (pintype "passive"))
    )
    (net (code "133") (name "unconnected-(J15-PadNORM)") (class "Default")
      (node (ref "J15") (pin "NORM") (pinfunction "NORM_NORM") (pintype "passive"))
    )
    (net (code "134") (name "unconnected-(J16-PadNORM)") (class "Default")
      (node (ref "J16") (pin "NORM") (pinfunction "NORM_NORM") (pintype "passive"))
    )
    (net (code "135") (name "unconnected-(LED5-RED-Pad3)") (class "Default")
      (node (ref "LED5") (pin "3") (pinfunction "RED_3") (pintype "bidirectional"))
    )
  )
)
